# Olympus_v2.net
KiCad netlist of a schematic drawn in EAGLE
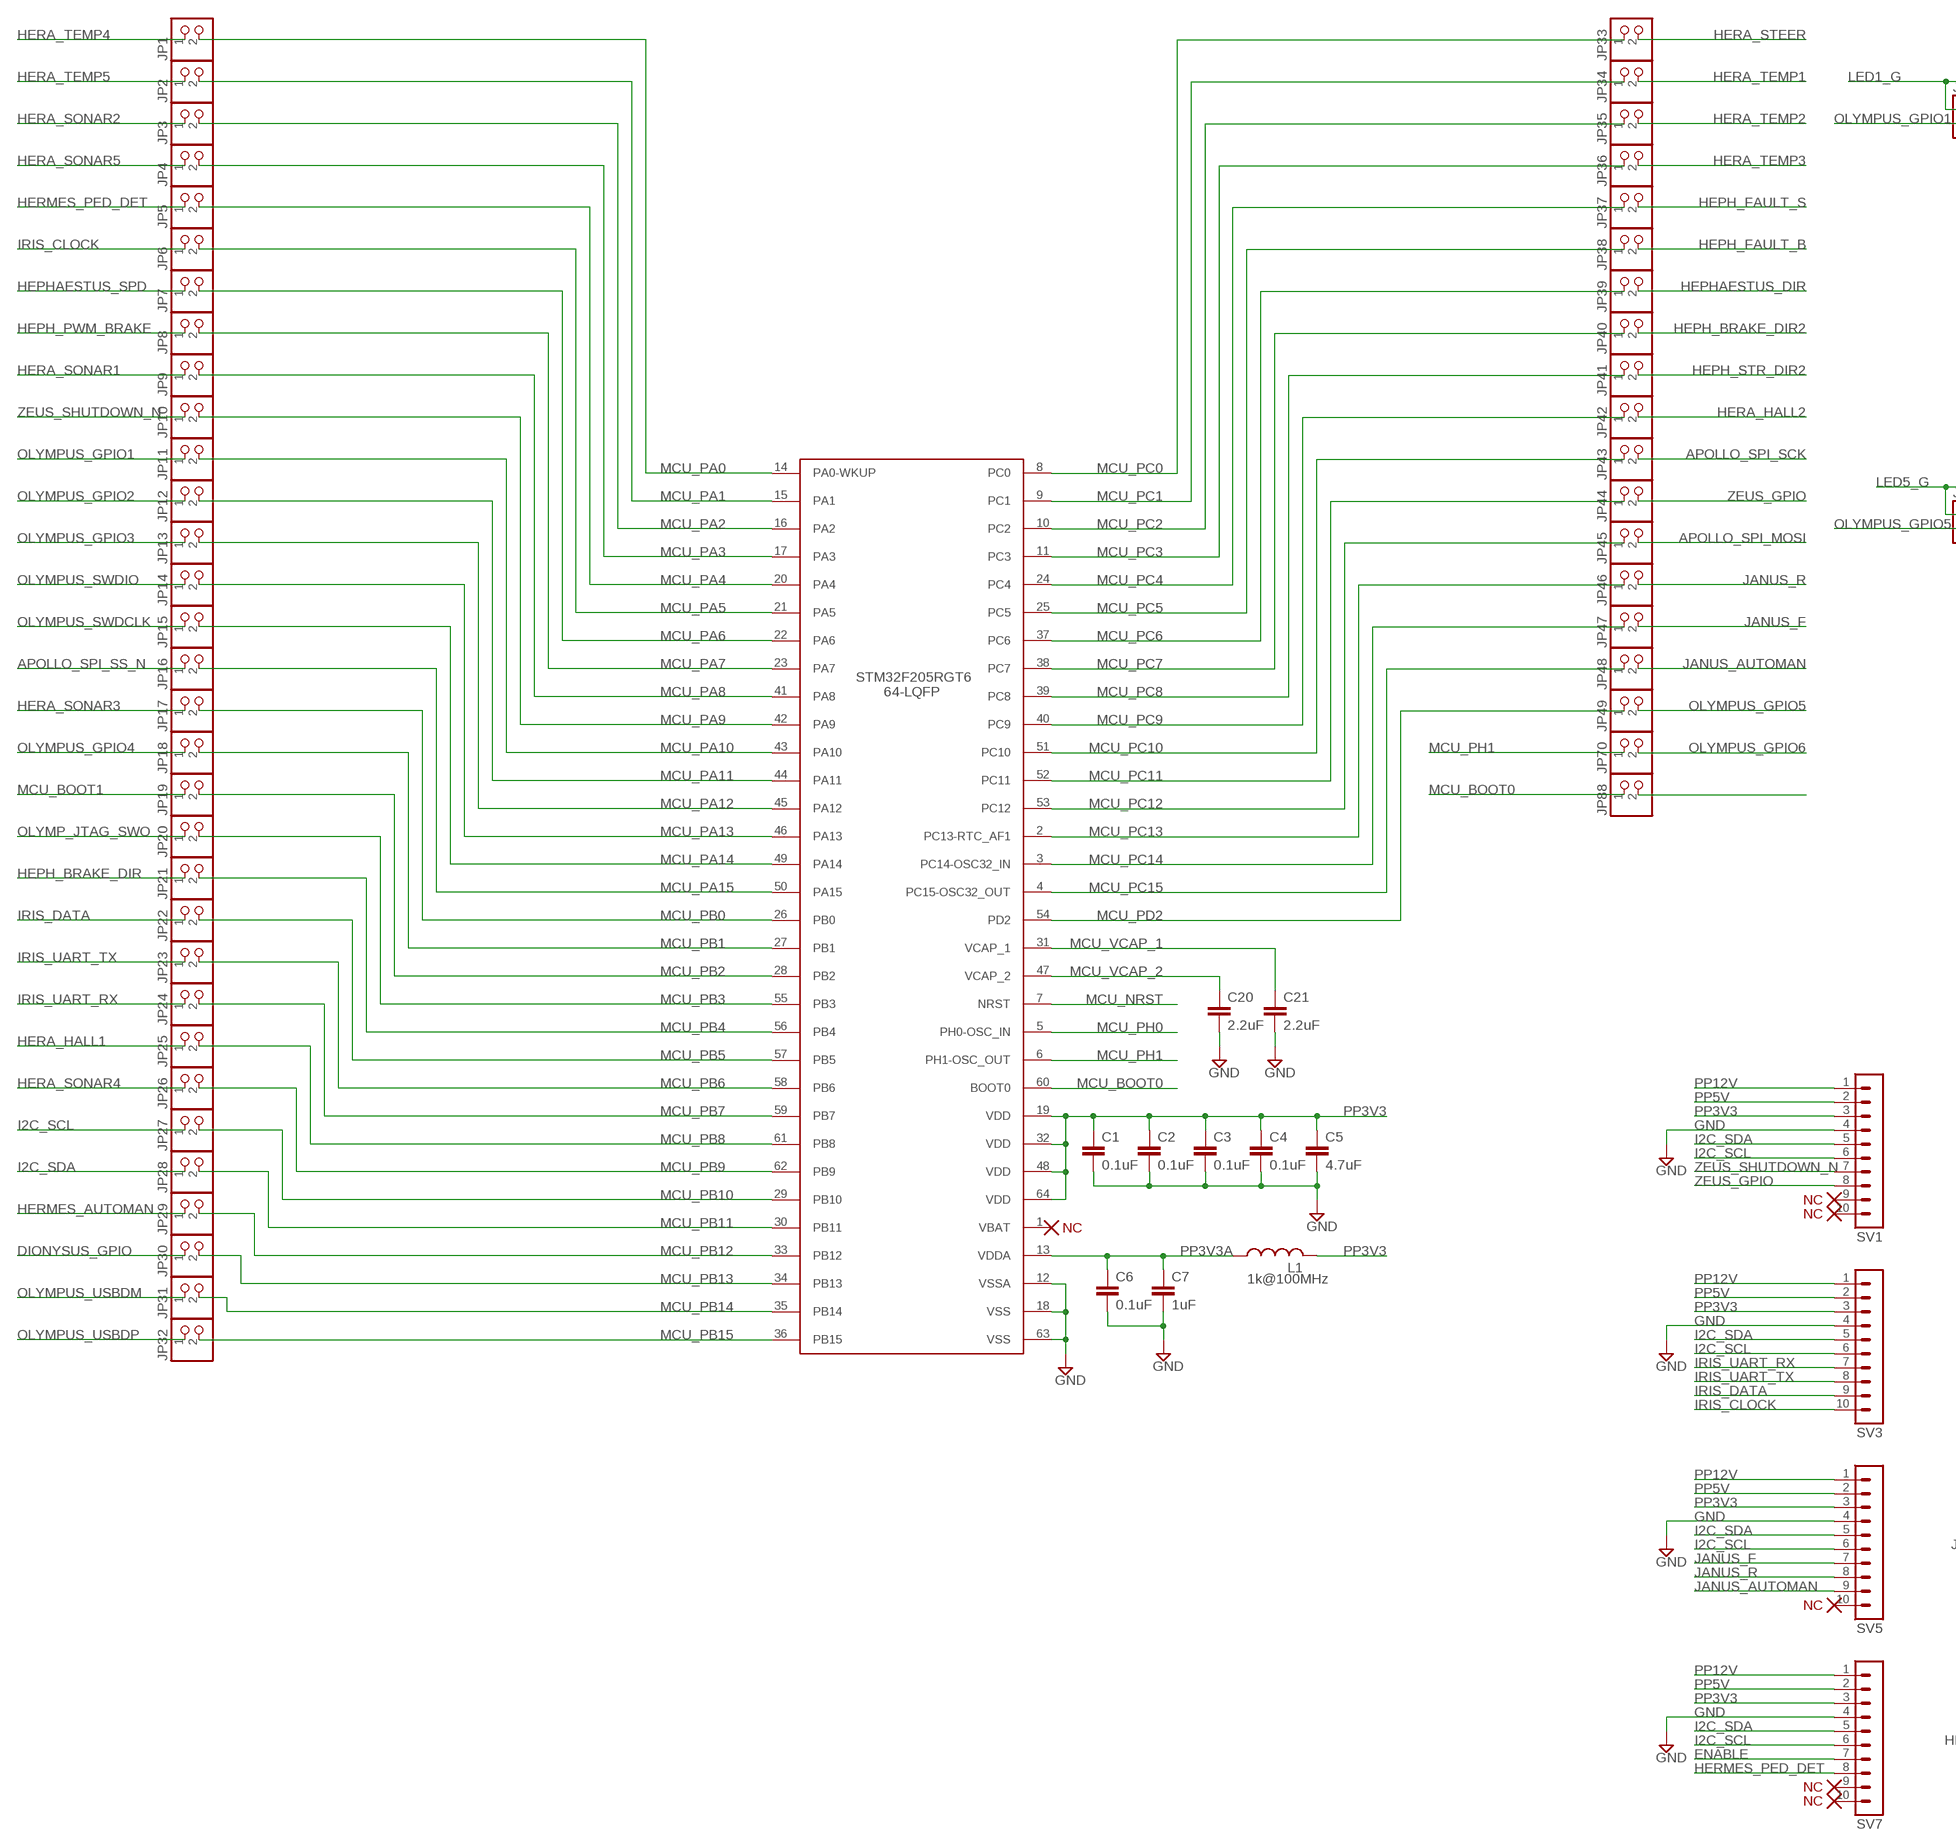
[diagram p0: schematic, sheet 1, part 1 of 2]
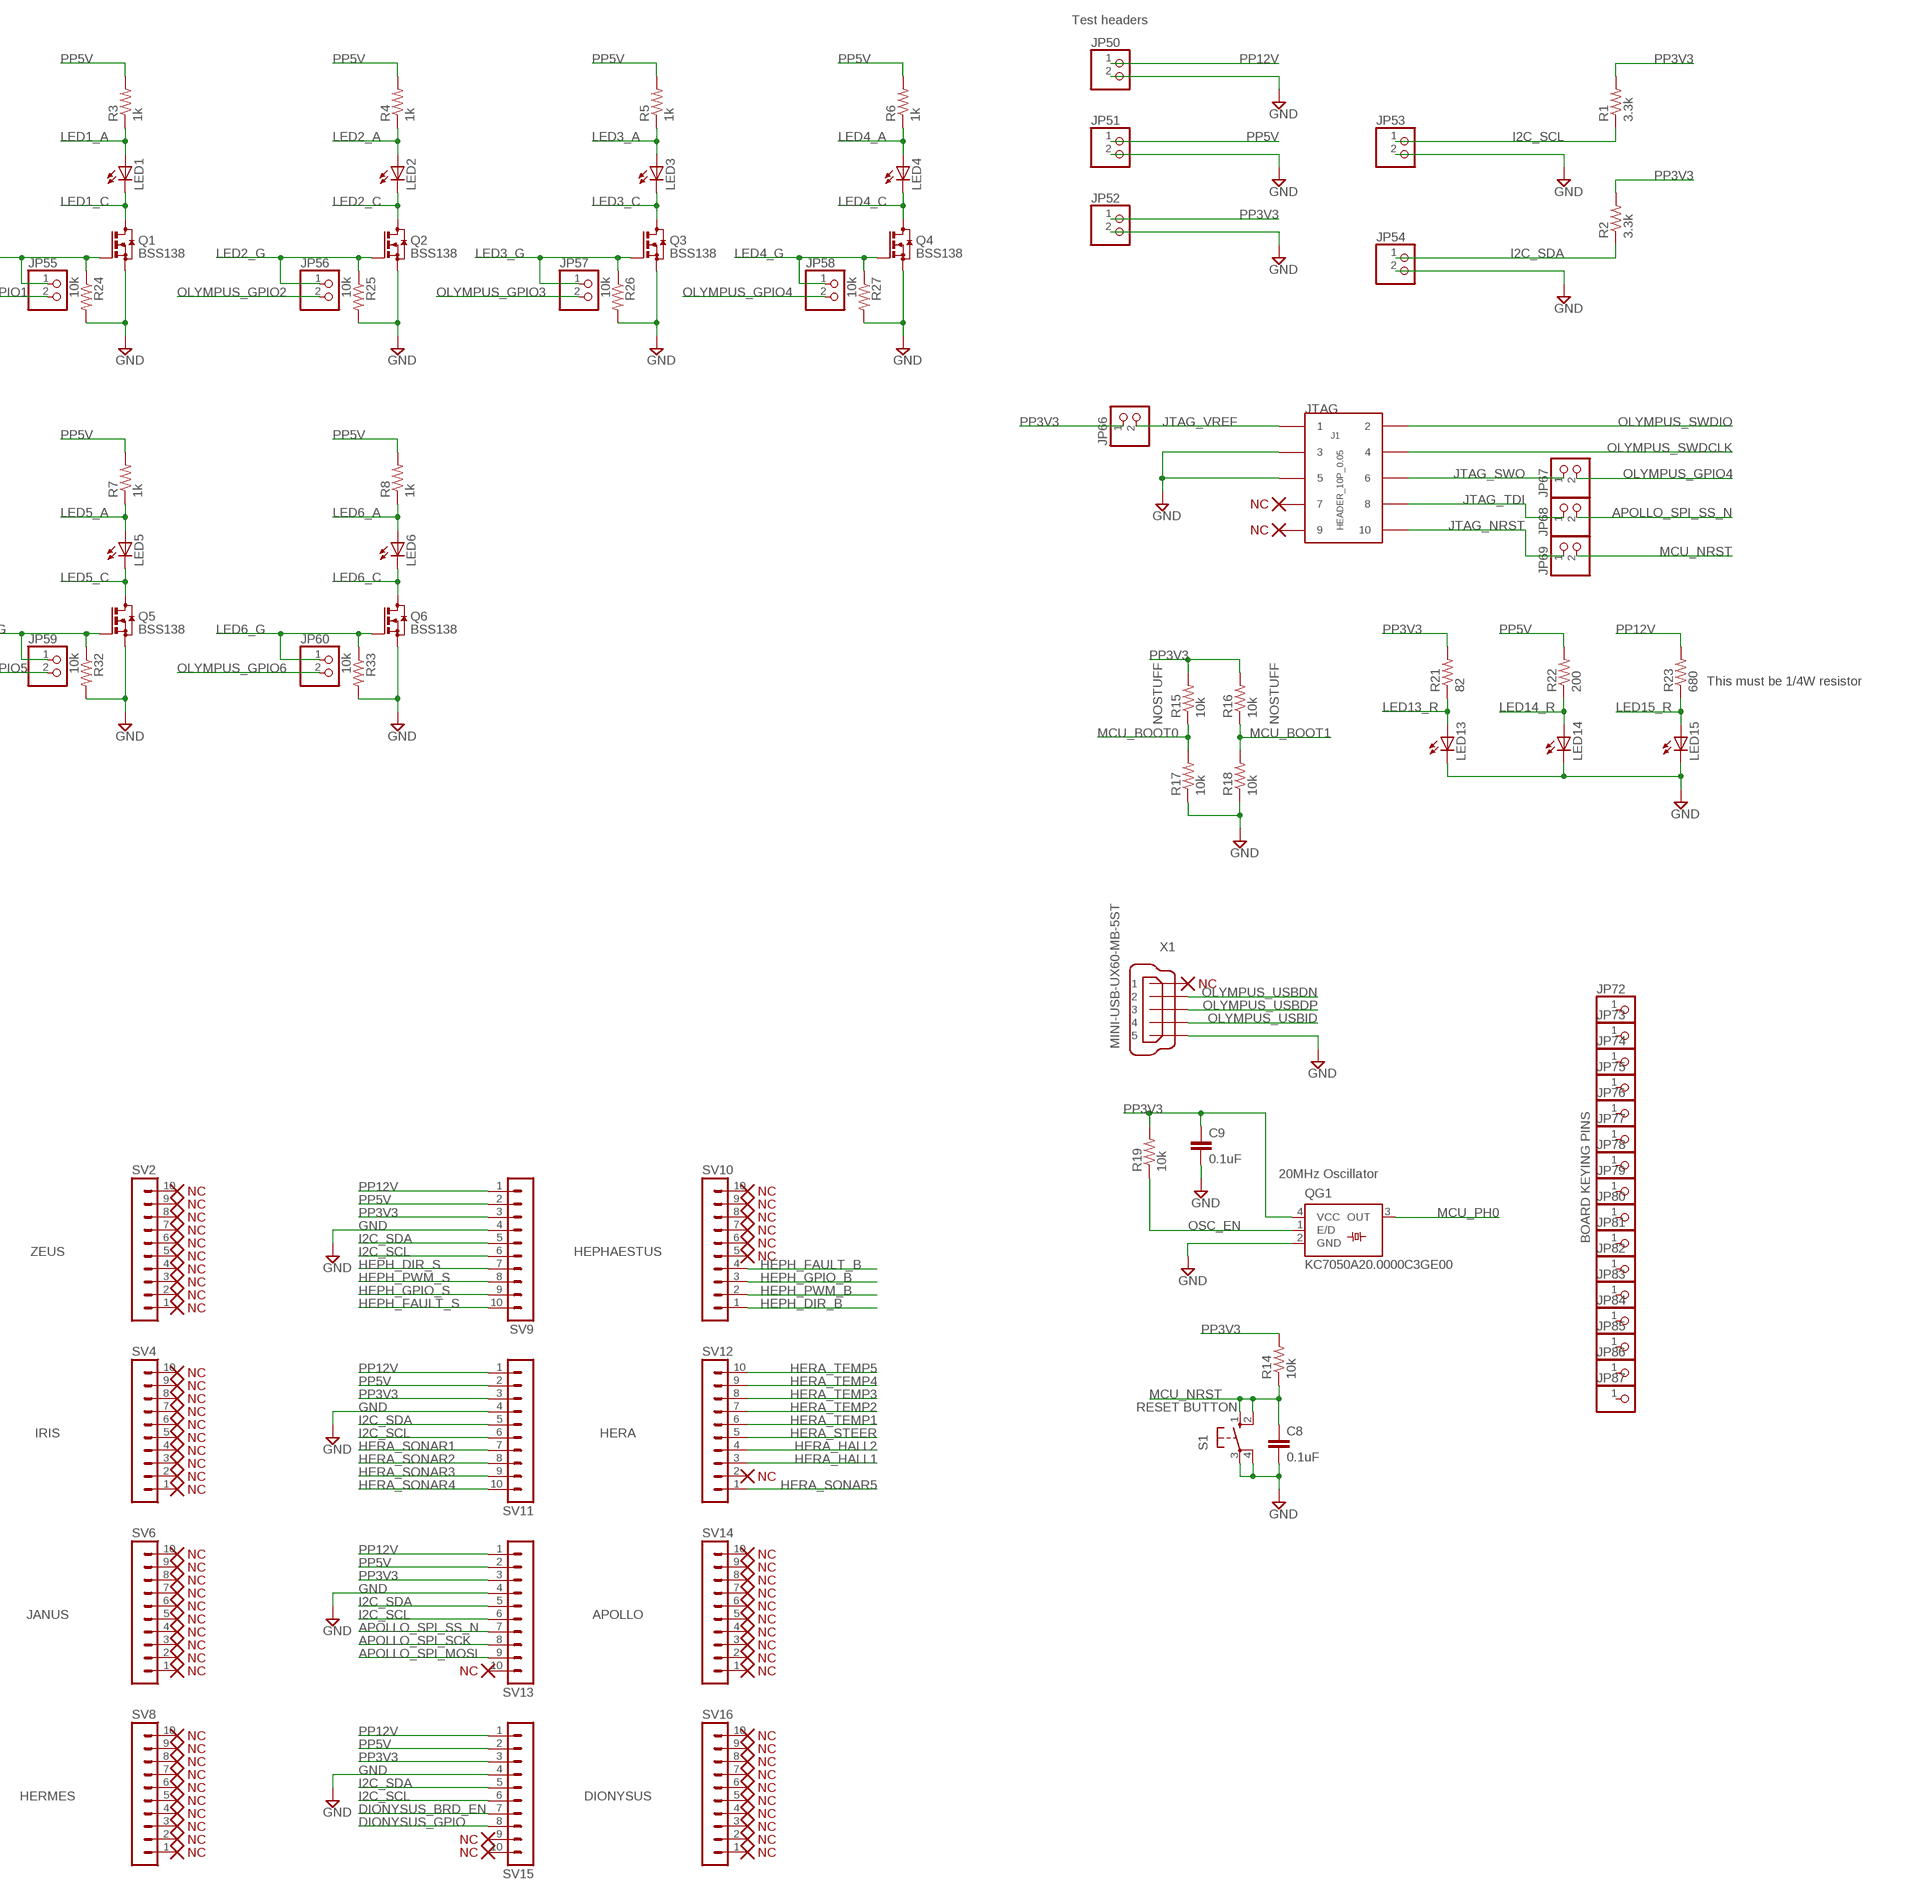
[diagram p1: schematic, sheet 1, part 2 of 2]

(export (version "E")
  (design (tool "Eeschema 10.0.6"))
  (components
    (comp (ref "C1")
      (value "0.1uF")
      (footprint "eagle-import:C0402")
      (libsource (lib "eagle-import") (part "C-EUC0402"))
    )
    (comp (ref "C2")
      (value "0.1uF")
      (footprint "eagle-import:C0402")
      (libsource (lib "eagle-import") (part "C-EUC0402"))
    )
    (comp (ref "C3")
      (value "0.1uF")
      (footprint "eagle-import:C0402")
      (libsource (lib "eagle-import") (part "C-EUC0402"))
    )
    (comp (ref "C4")
      (value "0.1uF")
      (footprint "eagle-import:C0402")
      (libsource (lib "eagle-import") (part "C-EUC0402"))
    )
    (comp (ref "C5")
      (value "4.7uF")
      (footprint "eagle-import:C0603")
      (libsource (lib "eagle-import") (part "C-EUC0603"))
    )
    (comp (ref "C6")
      (value "0.1uF")
      (footprint "eagle-import:C0402")
      (libsource (lib "eagle-import") (part "C-EUC0402"))
    )
    (comp (ref "C7")
      (value "1uF")
      (footprint "eagle-import:C0603")
      (libsource (lib "eagle-import") (part "C-EUC0603"))
    )
    (comp (ref "C8")
      (value "0.1uF")
      (footprint "eagle-import:C0402")
      (libsource (lib "eagle-import") (part "C-EUC0402"))
    )
    (comp (ref "C9")
      (value "0.1uF")
      (footprint "eagle-import:C0402")
      (libsource (lib "eagle-import") (part "C-EUC0402"))
    )
    (comp (ref "C20")
      (value "2.2uF")
      (footprint "eagle-import:C0402")
      (libsource (lib "eagle-import") (part "C-EUC0402"))
    )
    (comp (ref "C21")
      (value "2.2uF")
      (footprint "eagle-import:C0402")
      (libsource (lib "eagle-import") (part "C-EUC0402"))
    )
    (comp (ref "J1")
      (value "HEADER_10P_0.05")
      (footprint "eagle-import:HEADER_10P_0.05")
      (libsource (lib "eagle-import") (part "HEADER_10P_0.05"))
    )
    (comp (ref "JP1")
      (value "PINHD-1X2")
      (footprint "eagle-import:1X02")
      (libsource (lib "eagle-import") (part "PINHD-1X2"))
    )
    (comp (ref "JP2")
      (value "PINHD-1X2")
      (footprint "eagle-import:1X02")
      (libsource (lib "eagle-import") (part "PINHD-1X2"))
    )
    (comp (ref "JP3")
      (value "PINHD-1X2")
      (footprint "eagle-import:1X02")
      (libsource (lib "eagle-import") (part "PINHD-1X2"))
    )
    (comp (ref "JP4")
      (value "PINHD-1X2")
      (footprint "eagle-import:1X02")
      (libsource (lib "eagle-import") (part "PINHD-1X2"))
    )
    (comp (ref "JP5")
      (value "PINHD-1X2")
      (footprint "eagle-import:1X02")
      (libsource (lib "eagle-import") (part "PINHD-1X2"))
    )
    (comp (ref "JP6")
      (value "PINHD-1X2")
      (footprint "eagle-import:1X02")
      (libsource (lib "eagle-import") (part "PINHD-1X2"))
    )
    (comp (ref "JP7")
      (value "PINHD-1X2")
      (footprint "eagle-import:1X02")
      (libsource (lib "eagle-import") (part "PINHD-1X2"))
    )
    (comp (ref "JP8")
      (value "PINHD-1X2")
      (footprint "eagle-import:1X02")
      (libsource (lib "eagle-import") (part "PINHD-1X2"))
    )
    (comp (ref "JP9")
      (value "PINHD-1X2")
      (footprint "eagle-import:1X02")
      (libsource (lib "eagle-import") (part "PINHD-1X2"))
    )
    (comp (ref "JP10")
      (value "PINHD-1X2")
      (footprint "eagle-import:1X02")
      (libsource (lib "eagle-import") (part "PINHD-1X2"))
    )
    (comp (ref "JP11")
      (value "PINHD-1X2")
      (footprint "eagle-import:1X02")
      (libsource (lib "eagle-import") (part "PINHD-1X2"))
    )
    (comp (ref "JP12")
      (value "PINHD-1X2")
      (footprint "eagle-import:1X02")
      (libsource (lib "eagle-import") (part "PINHD-1X2"))
    )
    (comp (ref "JP13")
      (value "PINHD-1X2")
      (footprint "eagle-import:1X02")
      (libsource (lib "eagle-import") (part "PINHD-1X2"))
    )
    (comp (ref "JP14")
      (value "PINHD-1X2")
      (footprint "eagle-import:1X02")
      (libsource (lib "eagle-import") (part "PINHD-1X2"))
    )
    (comp (ref "JP15")
      (value "PINHD-1X2")
      (footprint "eagle-import:1X02")
      (libsource (lib "eagle-import") (part "PINHD-1X2"))
    )
    (comp (ref "JP16")
      (value "PINHD-1X2")
      (footprint "eagle-import:1X02")
      (libsource (lib "eagle-import") (part "PINHD-1X2"))
    )
    (comp (ref "JP17")
      (value "PINHD-1X2")
      (footprint "eagle-import:1X02")
      (libsource (lib "eagle-import") (part "PINHD-1X2"))
    )
    (comp (ref "JP18")
      (value "PINHD-1X2")
      (footprint "eagle-import:1X02")
      (libsource (lib "eagle-import") (part "PINHD-1X2"))
    )
    (comp (ref "JP19")
      (value "PINHD-1X2")
      (footprint "eagle-import:1X02")
      (libsource (lib "eagle-import") (part "PINHD-1X2"))
    )
    (comp (ref "JP20")
      (value "PINHD-1X2")
      (footprint "eagle-import:1X02")
      (libsource (lib "eagle-import") (part "PINHD-1X2"))
    )
    (comp (ref "JP21")
      (value "PINHD-1X2")
      (footprint "eagle-import:1X02")
      (libsource (lib "eagle-import") (part "PINHD-1X2"))
    )
    (comp (ref "JP22")
      (value "PINHD-1X2")
      (footprint "eagle-import:1X02")
      (libsource (lib "eagle-import") (part "PINHD-1X2"))
    )
    (comp (ref "JP23")
      (value "PINHD-1X2")
      (footprint "eagle-import:1X02")
      (libsource (lib "eagle-import") (part "PINHD-1X2"))
    )
    (comp (ref "JP24")
      (value "PINHD-1X2")
      (footprint "eagle-import:1X02")
      (libsource (lib "eagle-import") (part "PINHD-1X2"))
    )
    (comp (ref "JP25")
      (value "PINHD-1X2")
      (footprint "eagle-import:1X02")
      (libsource (lib "eagle-import") (part "PINHD-1X2"))
    )
    (comp (ref "JP26")
      (value "PINHD-1X2")
      (footprint "eagle-import:1X02")
      (libsource (lib "eagle-import") (part "PINHD-1X2"))
    )
    (comp (ref "JP27")
      (value "PINHD-1X2")
      (footprint "eagle-import:1X02")
      (libsource (lib "eagle-import") (part "PINHD-1X2"))
    )
    (comp (ref "JP28")
      (value "PINHD-1X2")
      (footprint "eagle-import:1X02")
      (libsource (lib "eagle-import") (part "PINHD-1X2"))
    )
    (comp (ref "JP29")
      (value "PINHD-1X2")
      (footprint "eagle-import:1X02")
      (libsource (lib "eagle-import") (part "PINHD-1X2"))
    )
    (comp (ref "JP30")
      (value "PINHD-1X2")
      (footprint "eagle-import:1X02")
      (libsource (lib "eagle-import") (part "PINHD-1X2"))
    )
    (comp (ref "JP31")
      (value "PINHD-1X2")
      (footprint "eagle-import:1X02")
      (libsource (lib "eagle-import") (part "PINHD-1X2"))
    )
    (comp (ref "JP32")
      (value "PINHD-1X2")
      (footprint "eagle-import:1X02")
      (libsource (lib "eagle-import") (part "PINHD-1X2"))
    )
    (comp (ref "JP33")
      (value "PINHD-1X2")
      (footprint "eagle-import:1X02")
      (libsource (lib "eagle-import") (part "PINHD-1X2"))
    )
    (comp (ref "JP34")
      (value "PINHD-1X2")
      (footprint "eagle-import:1X02")
      (libsource (lib "eagle-import") (part "PINHD-1X2"))
    )
    (comp (ref "JP35")
      (value "PINHD-1X2")
      (footprint "eagle-import:1X02")
      (libsource (lib "eagle-import") (part "PINHD-1X2"))
    )
    (comp (ref "JP36")
      (value "PINHD-1X2")
      (footprint "eagle-import:1X02")
      (libsource (lib "eagle-import") (part "PINHD-1X2"))
    )
    (comp (ref "JP37")
      (value "PINHD-1X2")
      (footprint "eagle-import:1X02")
      (libsource (lib "eagle-import") (part "PINHD-1X2"))
    )
    (comp (ref "JP38")
      (value "PINHD-1X2")
      (footprint "eagle-import:1X02")
      (libsource (lib "eagle-import") (part "PINHD-1X2"))
    )
    (comp (ref "JP39")
      (value "PINHD-1X2")
      (footprint "eagle-import:1X02")
      (libsource (lib "eagle-import") (part "PINHD-1X2"))
    )
    (comp (ref "JP40")
      (value "PINHD-1X2")
      (footprint "eagle-import:1X02")
      (libsource (lib "eagle-import") (part "PINHD-1X2"))
    )
    (comp (ref "JP41")
      (value "PINHD-1X2")
      (footprint "eagle-import:1X02")
      (libsource (lib "eagle-import") (part "PINHD-1X2"))
    )
    (comp (ref "JP42")
      (value "PINHD-1X2")
      (footprint "eagle-import:1X02")
      (libsource (lib "eagle-import") (part "PINHD-1X2"))
    )
    (comp (ref "JP43")
      (value "PINHD-1X2")
      (footprint "eagle-import:1X02")
      (libsource (lib "eagle-import") (part "PINHD-1X2"))
    )
    (comp (ref "JP44")
      (value "PINHD-1X2")
      (footprint "eagle-import:1X02")
      (libsource (lib "eagle-import") (part "PINHD-1X2"))
    )
    (comp (ref "JP45")
      (value "PINHD-1X2")
      (footprint "eagle-import:1X02")
      (libsource (lib "eagle-import") (part "PINHD-1X2"))
    )
    (comp (ref "JP46")
      (value "PINHD-1X2")
      (footprint "eagle-import:1X02")
      (libsource (lib "eagle-import") (part "PINHD-1X2"))
    )
    (comp (ref "JP47")
      (value "PINHD-1X2")
      (footprint "eagle-import:1X02")
      (libsource (lib "eagle-import") (part "PINHD-1X2"))
    )
    (comp (ref "JP48")
      (value "PINHD-1X2")
      (footprint "eagle-import:1X02")
      (libsource (lib "eagle-import") (part "PINHD-1X2"))
    )
    (comp (ref "JP49")
      (value "PINHD-1X2")
      (footprint "eagle-import:1X02")
      (libsource (lib "eagle-import") (part "PINHD-1X2"))
    )
    (comp (ref "JP50")
      (value "PINHD-1X2")
      (footprint "eagle-import:1X02")
      (libsource (lib "eagle-import") (part "PINHD-1X2"))
    )
    (comp (ref "JP51")
      (value "PINHD-1X2")
      (footprint "eagle-import:1X02")
      (libsource (lib "eagle-import") (part "PINHD-1X2"))
    )
    (comp (ref "JP52")
      (value "PINHD-1X2")
      (footprint "eagle-import:1X02")
      (libsource (lib "eagle-import") (part "PINHD-1X2"))
    )
    (comp (ref "JP53")
      (value "PINHD-1X2")
      (footprint "eagle-import:1X02")
      (libsource (lib "eagle-import") (part "PINHD-1X2"))
    )
    (comp (ref "JP54")
      (value "PINHD-1X2")
      (footprint "eagle-import:1X02")
      (libsource (lib "eagle-import") (part "PINHD-1X2"))
    )
    (comp (ref "JP55")
      (value "PINHD-1X2")
      (footprint "eagle-import:1X02")
      (libsource (lib "eagle-import") (part "PINHD-1X2"))
    )
    (comp (ref "JP56")
      (value "PINHD-1X2")
      (footprint "eagle-import:1X02")
      (libsource (lib "eagle-import") (part "PINHD-1X2"))
    )
    (comp (ref "JP57")
      (value "PINHD-1X2")
      (footprint "eagle-import:1X02")
      (libsource (lib "eagle-import") (part "PINHD-1X2"))
    )
    (comp (ref "JP58")
      (value "PINHD-1X2")
      (footprint "eagle-import:1X02")
      (libsource (lib "eagle-import") (part "PINHD-1X2"))
    )
    (comp (ref "JP59")
      (value "PINHD-1X2")
      (footprint "eagle-import:1X02")
      (libsource (lib "eagle-import") (part "PINHD-1X2"))
    )
    (comp (ref "JP60")
      (value "PINHD-1X2")
      (footprint "eagle-import:1X02")
      (libsource (lib "eagle-import") (part "PINHD-1X2"))
    )
    (comp (ref "JP66")
      (value "PINHD-1X2")
      (footprint "eagle-import:1X02")
      (libsource (lib "eagle-import") (part "PINHD-1X2"))
    )
    (comp (ref "JP67")
      (value "PINHD-1X2")
      (footprint "eagle-import:1X02")
      (libsource (lib "eagle-import") (part "PINHD-1X2"))
    )
    (comp (ref "JP68")
      (value "PINHD-1X2")
      (footprint "eagle-import:1X02")
      (libsource (lib "eagle-import") (part "PINHD-1X2"))
    )
    (comp (ref "JP69")
      (value "PINHD-1X2")
      (footprint "eagle-import:1X02")
      (libsource (lib "eagle-import") (part "PINHD-1X2"))
    )
    (comp (ref "JP70")
      (value "PINHD-1X2")
      (footprint "eagle-import:1X02")
      (libsource (lib "eagle-import") (part "PINHD-1X2"))
    )
    (comp (ref "JP72")
      (value "PINHD-1X1")
      (footprint "eagle-import:1X01")
      (libsource (lib "eagle-import") (part "PINHD-1X1"))
    )
    (comp (ref "JP73")
      (value "PINHD-1X1")
      (footprint "eagle-import:1X01")
      (libsource (lib "eagle-import") (part "PINHD-1X1"))
    )
    (comp (ref "JP74")
      (value "PINHD-1X1")
      (footprint "eagle-import:1X01")
      (libsource (lib "eagle-import") (part "PINHD-1X1"))
    )
    (comp (ref "JP75")
      (value "PINHD-1X1")
      (footprint "eagle-import:1X01")
      (libsource (lib "eagle-import") (part "PINHD-1X1"))
    )
    (comp (ref "JP76")
      (value "PINHD-1X1")
      (footprint "eagle-import:1X01")
      (libsource (lib "eagle-import") (part "PINHD-1X1"))
    )
    (comp (ref "JP77")
      (value "PINHD-1X1")
      (footprint "eagle-import:1X01")
      (libsource (lib "eagle-import") (part "PINHD-1X1"))
    )
    (comp (ref "JP78")
      (value "PINHD-1X1")
      (footprint "eagle-import:1X01")
      (libsource (lib "eagle-import") (part "PINHD-1X1"))
    )
    (comp (ref "JP79")
      (value "PINHD-1X1")
      (footprint "eagle-import:1X01")
      (libsource (lib "eagle-import") (part "PINHD-1X1"))
    )
    (comp (ref "JP80")
      (value "PINHD-1X1")
      (footprint "eagle-import:1X01")
      (libsource (lib "eagle-import") (part "PINHD-1X1"))
    )
    (comp (ref "JP81")
      (value "PINHD-1X1")
      (footprint "eagle-import:1X01")
      (libsource (lib "eagle-import") (part "PINHD-1X1"))
    )
    (comp (ref "JP82")
      (value "PINHD-1X1")
      (footprint "eagle-import:1X01")
      (libsource (lib "eagle-import") (part "PINHD-1X1"))
    )
    (comp (ref "JP83")
      (value "PINHD-1X1")
      (footprint "eagle-import:1X01")
      (libsource (lib "eagle-import") (part "PINHD-1X1"))
    )
    (comp (ref "JP84")
      (value "PINHD-1X1")
      (footprint "eagle-import:1X01")
      (libsource (lib "eagle-import") (part "PINHD-1X1"))
    )
    (comp (ref "JP85")
      (value "PINHD-1X1")
      (footprint "eagle-import:1X01")
      (libsource (lib "eagle-import") (part "PINHD-1X1"))
    )
    (comp (ref "JP86")
      (value "PINHD-1X1")
      (footprint "eagle-import:1X01")
      (libsource (lib "eagle-import") (part "PINHD-1X1"))
    )
    (comp (ref "JP87")
      (value "PINHD-1X1")
      (footprint "eagle-import:1X01")
      (libsource (lib "eagle-import") (part "PINHD-1X1"))
    )
    (comp (ref "JP88")
      (value "PINHD-1X2")
      (footprint "eagle-import:1X02")
      (libsource (lib "eagle-import") (part "PINHD-1X2"))
    )
    (comp (ref "L1")
      (value "L-USL0201")
      (footprint "eagle-import:L0201")
      (libsource (lib "eagle-import") (part "L-USL0201"))
    )
    (comp (ref "LED1")
      (value "LEDCHIP-LED0603")
      (footprint "eagle-import:CHIP-LED0603")
      (libsource (lib "eagle-import") (part "LEDCHIP-LED0603"))
    )
    (comp (ref "LED2")
      (value "LEDCHIP-LED0603")
      (footprint "eagle-import:CHIP-LED0603")
      (libsource (lib "eagle-import") (part "LEDCHIP-LED0603"))
    )
    (comp (ref "LED3")
      (value "LEDCHIP-LED0603")
      (footprint "eagle-import:CHIP-LED0603")
      (libsource (lib "eagle-import") (part "LEDCHIP-LED0603"))
    )
    (comp (ref "LED4")
      (value "LEDCHIP-LED0603")
      (footprint "eagle-import:CHIP-LED0603")
      (libsource (lib "eagle-import") (part "LEDCHIP-LED0603"))
    )
    (comp (ref "LED5")
      (value "LEDCHIP-LED0603")
      (footprint "eagle-import:CHIP-LED0603")
      (libsource (lib "eagle-import") (part "LEDCHIP-LED0603"))
    )
    (comp (ref "LED6")
      (value "LEDCHIP-LED0603")
      (footprint "eagle-import:CHIP-LED0603")
      (libsource (lib "eagle-import") (part "LEDCHIP-LED0603"))
    )
    (comp (ref "LED13")
      (value "LEDCHIP-LED0603")
      (footprint "eagle-import:CHIP-LED0603")
      (libsource (lib "eagle-import") (part "LEDCHIP-LED0603"))
    )
    (comp (ref "LED14")
      (value "LEDCHIP-LED0603")
      (footprint "eagle-import:CHIP-LED0603")
      (libsource (lib "eagle-import") (part "LEDCHIP-LED0603"))
    )
    (comp (ref "LED15")
      (value "LEDCHIP-LED0603")
      (footprint "eagle-import:CHIP-LED0603")
      (libsource (lib "eagle-import") (part "LEDCHIP-LED0603"))
    )
    (comp (ref "Q1")
      (value "BSS138")
      (footprint "eagle-import:SOT23")
      (libsource (lib "eagle-import") (part "BSS123"))
    )
    (comp (ref "Q2")
      (value "BSS138")
      (footprint "eagle-import:SOT23")
      (libsource (lib "eagle-import") (part "BSS123"))
    )
    (comp (ref "Q3")
      (value "BSS138")
      (footprint "eagle-import:SOT23")
      (libsource (lib "eagle-import") (part "BSS123"))
    )
    (comp (ref "Q4")
      (value "BSS138")
      (footprint "eagle-import:SOT23")
      (libsource (lib "eagle-import") (part "BSS123"))
    )
    (comp (ref "Q5")
      (value "BSS138")
      (footprint "eagle-import:SOT23")
      (libsource (lib "eagle-import") (part "BSS123"))
    )
    (comp (ref "Q6")
      (value "BSS138")
      (footprint "eagle-import:SOT23")
      (libsource (lib "eagle-import") (part "BSS123"))
    )
    (comp (ref "QG1")
      (value "KC7050A20.0000C3GE00")
      (footprint "eagle-import:SM77H")
      (libsource (lib "eagle-import") (part "SM77H"))
    )
    (comp (ref "R1")
      (value "3.3k")
      (footprint "eagle-import:R0603")
      (libsource (lib "eagle-import") (part "R-US_R0603"))
    )
    (comp (ref "R2")
      (value "3.3k")
      (footprint "eagle-import:R0603")
      (libsource (lib "eagle-import") (part "R-US_R0603"))
    )
    (comp (ref "R3")
      (value "1k")
      (footprint "eagle-import:R0603")
      (libsource (lib "eagle-import") (part "resistor_R-US_R0603"))
    )
    (comp (ref "R4")
      (value "1k")
      (footprint "eagle-import:R0603")
      (libsource (lib "eagle-import") (part "resistor_R-US_R0603"))
    )
    (comp (ref "R5")
      (value "1k")
      (footprint "eagle-import:R0603")
      (libsource (lib "eagle-import") (part "resistor_R-US_R0603"))
    )
    (comp (ref "R6")
      (value "1k")
      (footprint "eagle-import:R0603")
      (libsource (lib "eagle-import") (part "resistor_R-US_R0603"))
    )
    (comp (ref "R7")
      (value "1k")
      (footprint "eagle-import:R0603")
      (libsource (lib "eagle-import") (part "resistor_R-US_R0603"))
    )
    (comp (ref "R8")
      (value "1k")
      (footprint "eagle-import:R0603")
      (libsource (lib "eagle-import") (part "resistor_R-US_R0603"))
    )
    (comp (ref "R14")
      (value "10k")
      (footprint "eagle-import:R0603")
      (libsource (lib "eagle-import") (part "R-US_R0603"))
    )
    (comp (ref "R15")
      (value "10k")
      (footprint "eagle-import:R0603")
      (fields (field (name "BOMOPTION") "NOSTUFF"))
      (libsource (lib "eagle-import") (part "R-US_R0603"))
    )
    (comp (ref "R16")
      (value "10k")
      (footprint "eagle-import:R0603")
      (fields (field (name "BOMOPTION") "NOSTUFF"))
      (libsource (lib "eagle-import") (part "R-US_R0603"))
    )
    (comp (ref "R17")
      (value "10k")
      (footprint "eagle-import:R0603")
      (libsource (lib "eagle-import") (part "R-US_R0603"))
    )
    (comp (ref "R18")
      (value "10k")
      (footprint "eagle-import:R0603")
      (libsource (lib "eagle-import") (part "R-US_R0603"))
    )
    (comp (ref "R19")
      (value "10k")
      (footprint "eagle-import:R0603")
      (libsource (lib "eagle-import") (part "R-US_R0603"))
    )
    (comp (ref "R21")
      (value "82")
      (footprint "eagle-import:R0603")
      (libsource (lib "eagle-import") (part "resistor_R-US_R0603"))
    )
    (comp (ref "R22")
      (value "200")
      (footprint "eagle-import:R0603")
      (libsource (lib "eagle-import") (part "resistor_R-US_R0603"))
    )
    (comp (ref "R23")
      (value "680")
      (footprint "eagle-import:R0603")
      (libsource (lib "eagle-import") (part "resistor_R-US_R0603"))
    )
    (comp (ref "R24")
      (value "10k")
      (footprint "eagle-import:R0603")
      (libsource (lib "eagle-import") (part "resistor_R-US_R0603"))
    )
    (comp (ref "R25")
      (value "10k")
      (footprint "eagle-import:R0603")
      (libsource (lib "eagle-import") (part "resistor_R-US_R0603"))
    )
    (comp (ref "R26")
      (value "10k")
      (footprint "eagle-import:R0603")
      (libsource (lib "eagle-import") (part "resistor_R-US_R0603"))
    )
    (comp (ref "R27")
      (value "10k")
      (footprint "eagle-import:R0603")
      (libsource (lib "eagle-import") (part "resistor_R-US_R0603"))
    )
    (comp (ref "R32")
      (value "10k")
      (footprint "eagle-import:R0603")
      (libsource (lib "eagle-import") (part "resistor_R-US_R0603"))
    )
    (comp (ref "R33")
      (value "10k")
      (footprint "eagle-import:R0603")
      (libsource (lib "eagle-import") (part "resistor_R-US_R0603"))
    )
    (comp (ref "S1")
      (value "10-XX")
      (footprint "eagle-import:B3F-10XX")
      (fields (field (name "MPN") "B3F-1000"))
      (libsource (lib "eagle-import") (part "10-XX"))
    )
    (comp (ref "SV1")
      (value "MA10-1")
      (footprint "eagle-import:MA10-1")
      (libsource (lib "eagle-import") (part "MA10-1"))
    )
    (comp (ref "SV2")
      (value "MA10-1")
      (footprint "eagle-import:MA10-1")
      (libsource (lib "eagle-import") (part "MA10-1"))
    )
    (comp (ref "SV3")
      (value "MA10-1")
      (footprint "eagle-import:MA10-1")
      (libsource (lib "eagle-import") (part "MA10-1"))
    )
    (comp (ref "SV4")
      (value "MA10-1")
      (footprint "eagle-import:MA10-1")
      (libsource (lib "eagle-import") (part "MA10-1"))
    )
    (comp (ref "SV5")
      (value "MA10-1")
      (footprint "eagle-import:MA10-1")
      (libsource (lib "eagle-import") (part "MA10-1"))
    )
    (comp (ref "SV6")
      (value "MA10-1")
      (footprint "eagle-import:MA10-1")
      (libsource (lib "eagle-import") (part "MA10-1"))
    )
    (comp (ref "SV7")
      (value "MA10-1")
      (footprint "eagle-import:MA10-1")
      (libsource (lib "eagle-import") (part "MA10-1"))
    )
    (comp (ref "SV8")
      (value "MA10-1")
      (footprint "eagle-import:MA10-1")
      (libsource (lib "eagle-import") (part "MA10-1"))
    )
    (comp (ref "SV9")
      (value "MA10-1")
      (footprint "eagle-import:MA10-1")
      (libsource (lib "eagle-import") (part "MA10-1"))
    )
    (comp (ref "SV10")
      (value "MA10-1")
      (footprint "eagle-import:MA10-1")
      (libsource (lib "eagle-import") (part "MA10-1"))
    )
    (comp (ref "SV11")
      (value "MA10-1")
      (footprint "eagle-import:MA10-1")
      (libsource (lib "eagle-import") (part "MA10-1"))
    )
    (comp (ref "SV12")
      (value "MA10-1")
      (footprint "eagle-import:MA10-1")
      (libsource (lib "eagle-import") (part "MA10-1"))
    )
    (comp (ref "SV13")
      (value "MA10-1")
      (footprint "eagle-import:MA10-1")
      (libsource (lib "eagle-import") (part "MA10-1"))
    )
    (comp (ref "SV14")
      (value "MA10-1")
      (footprint "eagle-import:MA10-1")
      (libsource (lib "eagle-import") (part "MA10-1"))
    )
    (comp (ref "SV15")
      (value "MA10-1")
      (footprint "eagle-import:MA10-1")
      (libsource (lib "eagle-import") (part "MA10-1"))
    )
    (comp (ref "SV16")
      (value "MA10-1")
      (footprint "eagle-import:MA10-1")
      (libsource (lib "eagle-import") (part "MA10-1"))
    )
    (comp (ref "U1")
      (value "STM32F205RGT6")
      (footprint "eagle-import:LQFP-ST-64-2")
      (libsource (lib "eagle-import") (part "STM32F205RGT6"))
    )
    (comp (ref "X1")
      (value "MINI-USB-UX60-MB-5ST")
      (footprint "eagle-import:UX60-MB-5ST")
      (libsource (lib "eagle-import") (part "MINI-USB-UX60-MB-5ST"))
    )
  )
  (nets
    (net (code "1") (name "/APOLLO_SPI_MOSI") (class "Default")
      (node (ref "JP45") (pin "2") (pinfunction "2_2") (pintype "passive"))
      (node (ref "SV13") (pin "9") (pinfunction "9_9") (pintype "passive"))
    )
    (net (code "2") (name "/APOLLO_SPI_SCK") (class "Default")
      (node (ref "JP43") (pin "2") (pinfunction "2_2") (pintype "passive"))
      (node (ref "SV13") (pin "8") (pinfunction "8_8") (pintype "passive"))
    )
    (net (code "3") (name "/APOLLO_SPI_SS_N") (class "Default")
      (node (ref "JP16") (pin "1") (pinfunction "1_1") (pintype "passive"))
      (node (ref "JP68") (pin "2") (pinfunction "2_2") (pintype "passive"))
      (node (ref "SV13") (pin "7") (pinfunction "7_7") (pintype "passive"))
    )
    (net (code "4") (name "/DIONYSUS_BRD_EN") (class "Default")
      (node (ref "SV15") (pin "7") (pinfunction "7_7") (pintype "passive"))
    )
    (net (code "5") (name "/DIONYSUS_GPIO") (class "Default")
      (node (ref "JP30") (pin "1") (pinfunction "1_1") (pintype "passive"))
      (node (ref "SV15") (pin "8") (pinfunction "8_8") (pintype "passive"))
    )
    (net (code "6") (name "/ENABLE") (class "Default")
      (node (ref "SV7") (pin "7") (pinfunction "7_7") (pintype "passive"))
    )
    (net (code "7") (name "/HEPHAESTUS_DIR") (class "Default")
      (node (ref "JP39") (pin "2") (pinfunction "2_2") (pintype "passive"))
    )
    (net (code "8") (name "/HEPHAESTUS_SPD") (class "Default")
      (node (ref "JP7") (pin "1") (pinfunction "1_1") (pintype "passive"))
    )
    (net (code "9") (name "/HEPH_BRAKE_DIR") (class "Default")
      (node (ref "JP21") (pin "1") (pinfunction "1_1") (pintype "passive"))
    )
    (net (code "10") (name "/HEPH_BRAKE_DIR2") (class "Default")
      (node (ref "JP40") (pin "2") (pinfunction "2_2") (pintype "passive"))
    )
    (net (code "11") (name "/HEPH_DIR_B") (class "Default")
      (node (ref "SV10") (pin "1") (pinfunction "1_1") (pintype "passive"))
    )
    (net (code "12") (name "/HEPH_DIR_S") (class "Default")
      (node (ref "SV9") (pin "7") (pinfunction "7_7") (pintype "passive"))
    )
    (net (code "13") (name "/HEPH_FAULT_B") (class "Default")
      (node (ref "JP38") (pin "2") (pinfunction "2_2") (pintype "passive"))
      (node (ref "SV10") (pin "4") (pinfunction "4_4") (pintype "passive"))
    )
    (net (code "14") (name "/HEPH_FAULT_S") (class "Default")
      (node (ref "JP37") (pin "2") (pinfunction "2_2") (pintype "passive"))
      (node (ref "SV9") (pin "10") (pinfunction "10_10") (pintype "passive"))
    )
    (net (code "15") (name "/HEPH_GPIO_B") (class "Default")
      (node (ref "SV10") (pin "3") (pinfunction "3_3") (pintype "passive"))
    )
    (net (code "16") (name "/HEPH_GPIO_S") (class "Default")
      (node (ref "SV9") (pin "9") (pinfunction "9_9") (pintype "passive"))
    )
    (net (code "17") (name "/HEPH_PWM_B") (class "Default")
      (node (ref "SV10") (pin "2") (pinfunction "2_2") (pintype "passive"))
    )
    (net (code "18") (name "/HEPH_PWM_BRAKE") (class "Default")
      (node (ref "JP8") (pin "1") (pinfunction "1_1") (pintype "passive"))
    )
    (net (code "19") (name "/HEPH_PWM_S") (class "Default")
      (node (ref "SV9") (pin "8") (pinfunction "8_8") (pintype "passive"))
    )
    (net (code "20") (name "/HEPH_STR_DIR2") (class "Default")
      (node (ref "JP41") (pin "2") (pinfunction "2_2") (pintype "passive"))
    )
    (net (code "21") (name "/HERA_HALL1") (class "Default")
      (node (ref "JP25") (pin "1") (pinfunction "1_1") (pintype "passive"))
      (node (ref "SV12") (pin "3") (pinfunction "3_3") (pintype "passive"))
    )
    (net (code "22") (name "/HERA_HALL2") (class "Default")
      (node (ref "JP42") (pin "2") (pinfunction "2_2") (pintype "passive"))
      (node (ref "SV12") (pin "4") (pinfunction "4_4") (pintype "passive"))
    )
    (net (code "23") (name "/HERA_SONAR1") (class "Default")
      (node (ref "JP9") (pin "1") (pinfunction "1_1") (pintype "passive"))
      (node (ref "SV11") (pin "7") (pinfunction "7_7") (pintype "passive"))
    )
    (net (code "24") (name "/HERA_SONAR2") (class "Default")
      (node (ref "JP3") (pin "1") (pinfunction "1_1") (pintype "passive"))
      (node (ref "SV11") (pin "8") (pinfunction "8_8") (pintype "passive"))
    )
    (net (code "25") (name "/HERA_SONAR3") (class "Default")
      (node (ref "JP17") (pin "1") (pinfunction "1_1") (pintype "passive"))
      (node (ref "SV11") (pin "9") (pinfunction "9_9") (pintype "passive"))
    )
    (net (code "26") (name "/HERA_SONAR4") (class "Default")
      (node (ref "JP26") (pin "1") (pinfunction "1_1") (pintype "passive"))
      (node (ref "SV11") (pin "10") (pinfunction "10_10") (pintype "passive"))
    )
    (net (code "27") (name "/HERA_SONAR5") (class "Default")
      (node (ref "JP4") (pin "1") (pinfunction "1_1") (pintype "passive"))
      (node (ref "SV12") (pin "1") (pinfunction "1_1") (pintype "passive"))
    )
    (net (code "28") (name "/HERA_STEER") (class "Default")
      (node (ref "JP33") (pin "2") (pinfunction "2_2") (pintype "passive"))
      (node (ref "SV12") (pin "5") (pinfunction "5_5") (pintype "passive"))
    )
    (net (code "29") (name "/HERA_TEMP1") (class "Default")
      (node (ref "JP34") (pin "2") (pinfunction "2_2") (pintype "passive"))
      (node (ref "SV12") (pin "6") (pinfunction "6_6") (pintype "passive"))
    )
    (net (code "30") (name "/HERA_TEMP2") (class "Default")
      (node (ref "JP35") (pin "2") (pinfunction "2_2") (pintype "passive"))
      (node (ref "SV12") (pin "7") (pinfunction "7_7") (pintype "passive"))
    )
    (net (code "31") (name "/HERA_TEMP3") (class "Default")
      (node (ref "JP36") (pin "2") (pinfunction "2_2") (pintype "passive"))
      (node (ref "SV12") (pin "8") (pinfunction "8_8") (pintype "passive"))
    )
    (net (code "32") (name "/HERA_TEMP4") (class "Default")
      (node (ref "JP1") (pin "1") (pinfunction "1_1") (pintype "passive"))
      (node (ref "SV12") (pin "9") (pinfunction "9_9") (pintype "passive"))
    )
    (net (code "33") (name "/HERA_TEMP5") (class "Default")
      (node (ref "JP2") (pin "1") (pinfunction "1_1") (pintype "passive"))
      (node (ref "SV12") (pin "10") (pinfunction "10_10") (pintype "passive"))
    )
    (net (code "34") (name "/HERMES_AUTOMAN") (class "Default")
      (node (ref "JP29") (pin "1") (pinfunction "1_1") (pintype "passive"))
    )
    (net (code "35") (name "/HERMES_PED_DET") (class "Default")
      (node (ref "JP5") (pin "1") (pinfunction "1_1") (pintype "passive"))
      (node (ref "SV7") (pin "8") (pinfunction "8_8") (pintype "passive"))
    )
    (net (code "36") (name "/I2C_SCL") (class "Default")
      (node (ref "JP27") (pin "1") (pinfunction "1_1") (pintype "passive"))
      (node (ref "JP53") (pin "1") (pinfunction "1_1") (pintype "passive"))
      (node (ref "R1") (pin "1") (pinfunction "1_1") (pintype "passive"))
      (node (ref "SV1") (pin "6") (pinfunction "6_6") (pintype "passive"))
      (node (ref "SV11") (pin "6") (pinfunction "6_6") (pintype "passive"))
      (node (ref "SV13") (pin "6") (pinfunction "6_6") (pintype "passive"))
      (node (ref "SV15") (pin "6") (pinfunction "6_6") (pintype "passive"))
      (node (ref "SV3") (pin "6") (pinfunction "6_6") (pintype "passive"))
      (node (ref "SV5") (pin "6") (pinfunction "6_6") (pintype "passive"))
      (node (ref "SV7") (pin "6") (pinfunction "6_6") (pintype "passive"))
      (node (ref "SV9") (pin "6") (pinfunction "6_6") (pintype "passive"))
    )
    (net (code "37") (name "/I2C_SDA") (class "Default")
      (node (ref "JP28") (pin "1") (pinfunction "1_1") (pintype "passive"))
      (node (ref "JP54") (pin "1") (pinfunction "1_1") (pintype "passive"))
      (node (ref "R2") (pin "1") (pinfunction "1_1") (pintype "passive"))
      (node (ref "SV1") (pin "5") (pinfunction "5_5") (pintype "passive"))
      (node (ref "SV11") (pin "5") (pinfunction "5_5") (pintype "passive"))
      (node (ref "SV13") (pin "5") (pinfunction "5_5") (pintype "passive"))
      (node (ref "SV15") (pin "5") (pinfunction "5_5") (pintype "passive"))
      (node (ref "SV3") (pin "5") (pinfunction "5_5") (pintype "passive"))
      (node (ref "SV5") (pin "5") (pinfunction "5_5") (pintype "passive"))
      (node (ref "SV7") (pin "5") (pinfunction "5_5") (pintype "passive"))
      (node (ref "SV9") (pin "5") (pinfunction "5_5") (pintype "passive"))
    )
    (net (code "38") (name "/IRIS_CLOCK") (class "Default")
      (node (ref "JP6") (pin "1") (pinfunction "1_1") (pintype "passive"))
      (node (ref "SV3") (pin "10") (pinfunction "10_10") (pintype "passive"))
    )
    (net (code "39") (name "/IRIS_DATA") (class "Default")
      (node (ref "JP22") (pin "1") (pinfunction "1_1") (pintype "passive"))
      (node (ref "SV3") (pin "9") (pinfunction "9_9") (pintype "passive"))
    )
    (net (code "40") (name "/IRIS_UART_RX") (class "Default")
      (node (ref "JP24") (pin "1") (pinfunction "1_1") (pintype "passive"))
      (node (ref "SV3") (pin "7") (pinfunction "7_7") (pintype "passive"))
    )
    (net (code "41") (name "/IRIS_UART_TX") (class "Default")
      (node (ref "JP23") (pin "1") (pinfunction "1_1") (pintype "passive"))
      (node (ref "SV3") (pin "8") (pinfunction "8_8") (pintype "passive"))
    )
    (net (code "42") (name "/JANUS_AUTOMAN") (class "Default")
      (node (ref "JP48") (pin "2") (pinfunction "2_2") (pintype "passive"))
      (node (ref "SV5") (pin "9") (pinfunction "9_9") (pintype "passive"))
    )
    (net (code "43") (name "/JANUS_F") (class "Default")
      (node (ref "JP47") (pin "2") (pinfunction "2_2") (pintype "passive"))
      (node (ref "SV5") (pin "7") (pinfunction "7_7") (pintype "passive"))
    )
    (net (code "44") (name "/JANUS_R") (class "Default")
      (node (ref "JP46") (pin "2") (pinfunction "2_2") (pintype "passive"))
      (node (ref "SV5") (pin "8") (pinfunction "8_8") (pintype "passive"))
    )
    (net (code "45") (name "/JTAG_NRST") (class "Default")
      (node (ref "J1") (pin "10") (pinfunction "10_10") (pintype "bidirectional"))
      (node (ref "JP69") (pin "1") (pinfunction "1_1") (pintype "passive"))
    )
    (net (code "46") (name "/JTAG_SWO") (class "Default")
      (node (ref "J1") (pin "6") (pinfunction "6_6") (pintype "bidirectional"))
      (node (ref "JP67") (pin "1") (pinfunction "1_1") (pintype "passive"))
    )
    (net (code "47") (name "/JTAG_TDI") (class "Default")
      (node (ref "J1") (pin "8") (pinfunction "8_8") (pintype "bidirectional"))
      (node (ref "JP68") (pin "1") (pinfunction "1_1") (pintype "passive"))
    )
    (net (code "48") (name "/JTAG_VREF") (class "Default")
      (node (ref "J1") (pin "1") (pinfunction "1_1") (pintype "bidirectional"))
      (node (ref "JP66") (pin "2") (pinfunction "2_2") (pintype "passive"))
    )
    (net (code "49") (name "/LED1_A") (class "Default")
      (node (ref "LED1") (pin "A") (pinfunction "A_A") (pintype "passive"))
      (node (ref "R3") (pin "1") (pinfunction "1_1") (pintype "passive"))
    )
    (net (code "50") (name "/LED1_C") (class "Default")
      (node (ref "LED1") (pin "C") (pinfunction "C_C") (pintype "passive"))
      (node (ref "Q1") (pin "3") (pinfunction "D_3") (pintype "passive"))
    )
    (net (code "51") (name "/LED1_G") (class "Default")
      (node (ref "JP55") (pin "1") (pinfunction "1_1") (pintype "passive"))
      (node (ref "Q1") (pin "1") (pinfunction "G_1") (pintype "passive"))
      (node (ref "R24") (pin "1") (pinfunction "1_1") (pintype "passive"))
    )
    (net (code "52") (name "/LED2_A") (class "Default")
      (node (ref "LED2") (pin "A") (pinfunction "A_A") (pintype "passive"))
      (node (ref "R4") (pin "1") (pinfunction "1_1") (pintype "passive"))
    )
    (net (code "53") (name "/LED2_C") (class "Default")
      (node (ref "LED2") (pin "C") (pinfunction "C_C") (pintype "passive"))
      (node (ref "Q2") (pin "3") (pinfunction "D_3") (pintype "passive"))
    )
    (net (code "54") (name "/LED2_G") (class "Default")
      (node (ref "JP56") (pin "1") (pinfunction "1_1") (pintype "passive"))
      (node (ref "Q2") (pin "1") (pinfunction "G_1") (pintype "passive"))
      (node (ref "R25") (pin "1") (pinfunction "1_1") (pintype "passive"))
    )
    (net (code "55") (name "/LED3_A") (class "Default")
      (node (ref "LED3") (pin "A") (pinfunction "A_A") (pintype "passive"))
      (node (ref "R5") (pin "1") (pinfunction "1_1") (pintype "passive"))
    )
    (net (code "56") (name "/LED3_C") (class "Default")
      (node (ref "LED3") (pin "C") (pinfunction "C_C") (pintype "passive"))
      (node (ref "Q3") (pin "3") (pinfunction "D_3") (pintype "passive"))
    )
    (net (code "57") (name "/LED3_G") (class "Default")
      (node (ref "JP57") (pin "1") (pinfunction "1_1") (pintype "passive"))
      (node (ref "Q3") (pin "1") (pinfunction "G_1") (pintype "passive"))
      (node (ref "R26") (pin "1") (pinfunction "1_1") (pintype "passive"))
    )
    (net (code "58") (name "/LED4_A") (class "Default")
      (node (ref "LED4") (pin "A") (pinfunction "A_A") (pintype "passive"))
      (node (ref "R6") (pin "1") (pinfunction "1_1") (pintype "passive"))
    )
    (net (code "59") (name "/LED4_C") (class "Default")
      (node (ref "LED4") (pin "C") (pinfunction "C_C") (pintype "passive"))
      (node (ref "Q4") (pin "3") (pinfunction "D_3") (pintype "passive"))
    )
    (net (code "60") (name "/LED4_G") (class "Default")
      (node (ref "JP58") (pin "1") (pinfunction "1_1") (pintype "passive"))
      (node (ref "Q4") (pin "1") (pinfunction "G_1") (pintype "passive"))
      (node (ref "R27") (pin "1") (pinfunction "1_1") (pintype "passive"))
    )
    (net (code "61") (name "/LED5_A") (class "Default")
      (node (ref "LED5") (pin "A") (pinfunction "A_A") (pintype "passive"))
      (node (ref "R7") (pin "1") (pinfunction "1_1") (pintype "passive"))
    )
    (net (code "62") (name "/LED5_C") (class "Default")
      (node (ref "LED5") (pin "C") (pinfunction "C_C") (pintype "passive"))
      (node (ref "Q5") (pin "3") (pinfunction "D_3") (pintype "passive"))
    )
    (net (code "63") (name "/LED5_G") (class "Default")
      (node (ref "JP59") (pin "1") (pinfunction "1_1") (pintype "passive"))
      (node (ref "Q5") (pin "1") (pinfunction "G_1") (pintype "passive"))
      (node (ref "R32") (pin "1") (pinfunction "1_1") (pintype "passive"))
    )
    (net (code "64") (name "/LED6_A") (class "Default")
      (node (ref "LED6") (pin "A") (pinfunction "A_A") (pintype "passive"))
      (node (ref "R8") (pin "1") (pinfunction "1_1") (pintype "passive"))
    )
    (net (code "65") (name "/LED6_C") (class "Default")
      (node (ref "LED6") (pin "C") (pinfunction "C_C") (pintype "passive"))
      (node (ref "Q6") (pin "3") (pinfunction "D_3") (pintype "passive"))
    )
    (net (code "66") (name "/LED6_G") (class "Default")
      (node (ref "JP60") (pin "1") (pinfunction "1_1") (pintype "passive"))
      (node (ref "Q6") (pin "1") (pinfunction "G_1") (pintype "passive"))
      (node (ref "R33") (pin "1") (pinfunction "1_1") (pintype "passive"))
    )
    (net (code "67") (name "/LED13_R") (class "Default")
      (node (ref "LED13") (pin "A") (pinfunction "A_A") (pintype "passive"))
      (node (ref "R21") (pin "1") (pinfunction "1_1") (pintype "passive"))
    )
    (net (code "68") (name "/LED14_R") (class "Default")
      (node (ref "LED14") (pin "A") (pinfunction "A_A") (pintype "passive"))
      (node (ref "R22") (pin "1") (pinfunction "1_1") (pintype "passive"))
    )
    (net (code "69") (name "/LED15_R") (class "Default")
      (node (ref "LED15") (pin "A") (pinfunction "A_A") (pintype "passive"))
      (node (ref "R23") (pin "1") (pinfunction "1_1") (pintype "passive"))
    )
    (net (code "70") (name "/MCU_BOOT0") (class "Default")
      (node (ref "JP88") (pin "1") (pinfunction "1_1") (pintype "passive"))
      (node (ref "R15") (pin "1") (pinfunction "1_1") (pintype "passive"))
      (node (ref "R17") (pin "2") (pinfunction "2_2") (pintype "passive"))
      (node (ref "U1") (pin "60") (pinfunction "BOOT0_60") (pintype "bidirectional"))
    )
    (net (code "71") (name "/MCU_BOOT1") (class "Default")
      (node (ref "JP19") (pin "1") (pinfunction "1_1") (pintype "passive"))
      (node (ref "R16") (pin "1") (pinfunction "1_1") (pintype "passive"))
      (node (ref "R18") (pin "2") (pinfunction "2_2") (pintype "passive"))
    )
    (net (code "72") (name "/MCU_NRST") (class "Default")
      (node (ref "C8") (pin "1") (pinfunction "1_1") (pintype "passive"))
      (node (ref "JP69") (pin "2") (pinfunction "2_2") (pintype "passive"))
      (node (ref "R14") (pin "1") (pinfunction "1_1") (pintype "passive"))
      (node (ref "S1") (pin "1") (pinfunction "S_1") (pintype "passive"))
      (node (ref "S1") (pin "2") (pinfunction "S1_2") (pintype "passive"))
      (node (ref "U1") (pin "7") (pinfunction "NRST_7") (pintype "bidirectional"))
    )
    (net (code "73") (name "/MCU_PA0") (class "Default")
      (node (ref "JP1") (pin "2") (pinfunction "2_2") (pintype "passive"))
      (node (ref "U1") (pin "14") (pinfunction "PA0-WKUP_14") (pintype "bidirectional"))
    )
    (net (code "74") (name "/MCU_PA1") (class "Default")
      (node (ref "JP2") (pin "2") (pinfunction "2_2") (pintype "passive"))
      (node (ref "U1") (pin "15") (pinfunction "PA1_15") (pintype "bidirectional"))
    )
    (net (code "75") (name "/MCU_PA2") (class "Default")
      (node (ref "JP3") (pin "2") (pinfunction "2_2") (pintype "passive"))
      (node (ref "U1") (pin "16") (pinfunction "PA2_16") (pintype "bidirectional"))
    )
    (net (code "76") (name "/MCU_PA3") (class "Default")
      (node (ref "JP4") (pin "2") (pinfunction "2_2") (pintype "passive"))
      (node (ref "U1") (pin "17") (pinfunction "PA3_17") (pintype "bidirectional"))
    )
    (net (code "77") (name "/MCU_PA4") (class "Default")
      (node (ref "JP5") (pin "2") (pinfunction "2_2") (pintype "passive"))
      (node (ref "U1") (pin "20") (pinfunction "PA4_20") (pintype "bidirectional"))
    )
    (net (code "78") (name "/MCU_PA5") (class "Default")
      (node (ref "JP6") (pin "2") (pinfunction "2_2") (pintype "passive"))
      (node (ref "U1") (pin "21") (pinfunction "PA5_21") (pintype "bidirectional"))
    )
    (net (code "79") (name "/MCU_PA6") (class "Default")
      (node (ref "JP7") (pin "2") (pinfunction "2_2") (pintype "passive"))
      (node (ref "U1") (pin "22") (pinfunction "PA6_22") (pintype "bidirectional"))
    )
    (net (code "80") (name "/MCU_PA7") (class "Default")
      (node (ref "JP8") (pin "2") (pinfunction "2_2") (pintype "passive"))
      (node (ref "U1") (pin "23") (pinfunction "PA7_23") (pintype "bidirectional"))
    )
    (net (code "81") (name "/MCU_PA8") (class "Default")
      (node (ref "JP9") (pin "2") (pinfunction "2_2") (pintype "passive"))
      (node (ref "U1") (pin "41") (pinfunction "PA8_41") (pintype "bidirectional"))
    )
    (net (code "82") (name "/MCU_PA9") (class "Default")
      (node (ref "JP10") (pin "2") (pinfunction "2_2") (pintype "passive"))
      (node (ref "U1") (pin "42") (pinfunction "PA9_42") (pintype "bidirectional"))
    )
    (net (code "83") (name "/MCU_PA10") (class "Default")
      (node (ref "JP11") (pin "2") (pinfunction "2_2") (pintype "passive"))
      (node (ref "U1") (pin "43") (pinfunction "PA10_43") (pintype "bidirectional"))
    )
    (net (code "84") (name "/MCU_PA11") (class "Default")
      (node (ref "JP12") (pin "2") (pinfunction "2_2") (pintype "passive"))
      (node (ref "U1") (pin "44") (pinfunction "PA11_44") (pintype "bidirectional"))
    )
    (net (code "85") (name "/MCU_PA12") (class "Default")
      (node (ref "JP13") (pin "2") (pinfunction "2_2") (pintype "passive"))
      (node (ref "U1") (pin "45") (pinfunction "PA12_45") (pintype "bidirectional"))
    )
    (net (code "86") (name "/MCU_PA13") (class "Default")
      (node (ref "JP14") (pin "2") (pinfunction "2_2") (pintype "passive"))
      (node (ref "U1") (pin "46") (pinfunction "PA13_46") (pintype "bidirectional"))
    )
    (net (code "87") (name "/MCU_PA14") (class "Default")
      (node (ref "JP15") (pin "2") (pinfunction "2_2") (pintype "passive"))
      (node (ref "U1") (pin "49") (pinfunction "PA14_49") (pintype "bidirectional"))
    )
    (net (code "88") (name "/MCU_PA15") (class "Default")
      (node (ref "JP16") (pin "2") (pinfunction "2_2") (pintype "passive"))
      (node (ref "U1") (pin "50") (pinfunction "PA15_50") (pintype "bidirectional"))
    )
    (net (code "89") (name "/MCU_PB0") (class "Default")
      (node (ref "JP17") (pin "2") (pinfunction "2_2") (pintype "passive"))
      (node (ref "U1") (pin "26") (pinfunction "PB0_26") (pintype "bidirectional"))
    )
    (net (code "90") (name "/MCU_PB1") (class "Default")
      (node (ref "JP18") (pin "2") (pinfunction "2_2") (pintype "passive"))
      (node (ref "U1") (pin "27") (pinfunction "PB1_27") (pintype "bidirectional"))
    )
    (net (code "91") (name "/MCU_PB2") (class "Default")
      (node (ref "JP19") (pin "2") (pinfunction "2_2") (pintype "passive"))
      (node (ref "U1") (pin "28") (pinfunction "PB2_28") (pintype "bidirectional"))
    )
    (net (code "92") (name "/MCU_PB3") (class "Default")
      (node (ref "JP20") (pin "2") (pinfunction "2_2") (pintype "passive"))
      (node (ref "U1") (pin "55") (pinfunction "PB3_55") (pintype "bidirectional"))
    )
    (net (code "93") (name "/MCU_PB4") (class "Default")
      (node (ref "JP21") (pin "2") (pinfunction "2_2") (pintype "passive"))
      (node (ref "U1") (pin "56") (pinfunction "PB4_56") (pintype "bidirectional"))
    )
    (net (code "94") (name "/MCU_PB5") (class "Default")
      (node (ref "JP22") (pin "2") (pinfunction "2_2") (pintype "passive"))
      (node (ref "U1") (pin "57") (pinfunction "PB5_57") (pintype "bidirectional"))
    )
    (net (code "95") (name "/MCU_PB6") (class "Default")
      (node (ref "JP23") (pin "2") (pinfunction "2_2") (pintype "passive"))
      (node (ref "U1") (pin "58") (pinfunction "PB6_58") (pintype "bidirectional"))
    )
    (net (code "96") (name "/MCU_PB7") (class "Default")
      (node (ref "JP24") (pin "2") (pinfunction "2_2") (pintype "passive"))
      (node (ref "U1") (pin "59") (pinfunction "PB7_59") (pintype "bidirectional"))
    )
    (net (code "97") (name "/MCU_PB8") (class "Default")
      (node (ref "JP25") (pin "2") (pinfunction "2_2") (pintype "passive"))
      (node (ref "U1") (pin "61") (pinfunction "PB8_61") (pintype "bidirectional"))
    )
    (net (code "98") (name "/MCU_PB9") (class "Default")
      (node (ref "JP26") (pin "2") (pinfunction "2_2") (pintype "passive"))
      (node (ref "U1") (pin "62") (pinfunction "PB9_62") (pintype "bidirectional"))
    )
    (net (code "99") (name "/MCU_PB10") (class "Default")
      (node (ref "JP27") (pin "2") (pinfunction "2_2") (pintype "passive"))
      (node (ref "U1") (pin "29") (pinfunction "PB10_29") (pintype "bidirectional"))
    )
    (net (code "100") (name "/MCU_PB11") (class "Default")
      (node (ref "JP28") (pin "2") (pinfunction "2_2") (pintype "passive"))
      (node (ref "U1") (pin "30") (pinfunction "PB11_30") (pintype "bidirectional"))
    )
    (net (code "101") (name "/MCU_PB12") (class "Default")
      (node (ref "JP29") (pin "2") (pinfunction "2_2") (pintype "passive"))
      (node (ref "U1") (pin "33") (pinfunction "PB12_33") (pintype "bidirectional"))
    )
    (net (code "102") (name "/MCU_PB13") (class "Default")
      (node (ref "JP30") (pin "2") (pinfunction "2_2") (pintype "passive"))
      (node (ref "U1") (pin "34") (pinfunction "PB13_34") (pintype "bidirectional"))
    )
    (net (code "103") (name "/MCU_PB14") (class "Default")
      (node (ref "JP31") (pin "2") (pinfunction "2_2") (pintype "passive"))
      (node (ref "U1") (pin "35") (pinfunction "PB14_35") (pintype "bidirectional"))
    )
    (net (code "104") (name "/MCU_PB15") (class "Default")
      (node (ref "JP32") (pin "2") (pinfunction "2_2") (pintype "passive"))
      (node (ref "U1") (pin "36") (pinfunction "PB15_36") (pintype "bidirectional"))
    )
    (net (code "105") (name "/MCU_PC0") (class "Default")
      (node (ref "JP33") (pin "1") (pinfunction "1_1") (pintype "passive"))
      (node (ref "U1") (pin "8") (pinfunction "PC0_8") (pintype "bidirectional"))
    )
    (net (code "106") (name "/MCU_PC1") (class "Default")
      (node (ref "JP34") (pin "1") (pinfunction "1_1") (pintype "passive"))
      (node (ref "U1") (pin "9") (pinfunction "PC1_9") (pintype "bidirectional"))
    )
    (net (code "107") (name "/MCU_PC2") (class "Default")
      (node (ref "JP35") (pin "1") (pinfunction "1_1") (pintype "passive"))
      (node (ref "U1") (pin "10") (pinfunction "PC2_10") (pintype "bidirectional"))
    )
    (net (code "108") (name "/MCU_PC3") (class "Default")
      (node (ref "JP36") (pin "1") (pinfunction "1_1") (pintype "passive"))
      (node (ref "U1") (pin "11") (pinfunction "PC3_11") (pintype "bidirectional"))
    )
    (net (code "109") (name "/MCU_PC4") (class "Default")
      (node (ref "JP37") (pin "1") (pinfunction "1_1") (pintype "passive"))
      (node (ref "U1") (pin "24") (pinfunction "PC4_24") (pintype "bidirectional"))
    )
    (net (code "110") (name "/MCU_PC5") (class "Default")
      (node (ref "JP38") (pin "1") (pinfunction "1_1") (pintype "passive"))
      (node (ref "U1") (pin "25") (pinfunction "PC5_25") (pintype "bidirectional"))
    )
    (net (code "111") (name "/MCU_PC6") (class "Default")
      (node (ref "JP39") (pin "1") (pinfunction "1_1") (pintype "passive"))
      (node (ref "U1") (pin "37") (pinfunction "PC6_37") (pintype "bidirectional"))
    )
    (net (code "112") (name "/MCU_PC7") (class "Default")
      (node (ref "JP40") (pin "1") (pinfunction "1_1") (pintype "passive"))
      (node (ref "U1") (pin "38") (pinfunction "PC7_38") (pintype "bidirectional"))
    )
    (net (code "113") (name "/MCU_PC8") (class "Default")
      (node (ref "JP41") (pin "1") (pinfunction "1_1") (pintype "passive"))
      (node (ref "U1") (pin "39") (pinfunction "PC8_39") (pintype "bidirectional"))
    )
    (net (code "114") (name "/MCU_PC9") (class "Default")
      (node (ref "JP42") (pin "1") (pinfunction "1_1") (pintype "passive"))
      (node (ref "U1") (pin "40") (pinfunction "PC9_40") (pintype "bidirectional"))
    )
    (net (code "115") (name "/MCU_PC10") (class "Default")
      (node (ref "JP43") (pin "1") (pinfunction "1_1") (pintype "passive"))
      (node (ref "U1") (pin "51") (pinfunction "PC10_51") (pintype "bidirectional"))
    )
    (net (code "116") (name "/MCU_PC11") (class "Default")
      (node (ref "JP44") (pin "1") (pinfunction "1_1") (pintype "passive"))
      (node (ref "U1") (pin "52") (pinfunction "PC11_52") (pintype "bidirectional"))
    )
    (net (code "117") (name "/MCU_PC12") (class "Default")
      (node (ref "JP45") (pin "1") (pinfunction "1_1") (pintype "passive"))
      (node (ref "U1") (pin "53") (pinfunction "PC12_53") (pintype "bidirectional"))
    )
    (net (code "118") (name "/MCU_PC13") (class "Default")
      (node (ref "JP46") (pin "1") (pinfunction "1_1") (pintype "passive"))
      (node (ref "U1") (pin "2") (pinfunction "PC13-RTC_AF1_2") (pintype "bidirectional"))
    )
    (net (code "119") (name "/MCU_PC14") (class "Default")
      (node (ref "JP47") (pin "1") (pinfunction "1_1") (pintype "passive"))
      (node (ref "U1") (pin "3") (pinfunction "PC14-OSC32_IN_3") (pintype "bidirectional"))
    )
    (net (code "120") (name "/MCU_PC15") (class "Default")
      (node (ref "JP48") (pin "1") (pinfunction "1_1") (pintype "passive"))
      (node (ref "U1") (pin "4") (pinfunction "PC15-OSC32_OUT_4") (pintype "bidirectional"))
    )
    (net (code "121") (name "/MCU_PD2") (class "Default")
      (node (ref "JP49") (pin "1") (pinfunction "1_1") (pintype "passive"))
      (node (ref "U1") (pin "54") (pinfunction "PD2_54") (pintype "bidirectional"))
    )
    (net (code "122") (name "/MCU_PH0") (class "Default")
      (node (ref "QG1") (pin "3") (pinfunction "OUT_3") (pintype "output"))
      (node (ref "U1") (pin "5") (pinfunction "PH0-OSC_IN_5") (pintype "bidirectional"))
    )
    (net (code "123") (name "/MCU_PH1") (class "Default")
      (node (ref "JP70") (pin "1") (pinfunction "1_1") (pintype "passive"))
      (node (ref "U1") (pin "6") (pinfunction "PH1-OSC_OUT_6") (pintype "bidirectional"))
    )
    (net (code "124") (name "/MCU_VCAP_1") (class "Default")
      (node (ref "C21") (pin "1") (pinfunction "1_1") (pintype "passive"))
      (node (ref "U1") (pin "31") (pinfunction "VCAP_1_31") (pintype "bidirectional"))
    )
    (net (code "125") (name "/MCU_VCAP_2") (class "Default")
      (node (ref "C20") (pin "1") (pinfunction "1_1") (pintype "passive"))
      (node (ref "U1") (pin "47") (pinfunction "VCAP_2_47") (pintype "bidirectional"))
    )
    (net (code "126") (name "/OLYMPUS_GPIO1") (class "Default")
      (node (ref "JP11") (pin "1") (pinfunction "1_1") (pintype "passive"))
      (node (ref "JP55") (pin "2") (pinfunction "2_2") (pintype "passive"))
    )
    (net (code "127") (name "/OLYMPUS_GPIO2") (class "Default")
      (node (ref "JP12") (pin "1") (pinfunction "1_1") (pintype "passive"))
      (node (ref "JP56") (pin "2") (pinfunction "2_2") (pintype "passive"))
    )
    (net (code "128") (name "/OLYMPUS_GPIO3") (class "Default")
      (node (ref "JP13") (pin "1") (pinfunction "1_1") (pintype "passive"))
      (node (ref "JP57") (pin "2") (pinfunction "2_2") (pintype "passive"))
    )
    (net (code "129") (name "/OLYMPUS_GPIO4") (class "Default")
      (node (ref "JP18") (pin "1") (pinfunction "1_1") (pintype "passive"))
      (node (ref "JP58") (pin "2") (pinfunction "2_2") (pintype "passive"))
      (node (ref "JP67") (pin "2") (pinfunction "2_2") (pintype "passive"))
    )
    (net (code "130") (name "/OLYMPUS_GPIO5") (class "Default")
      (node (ref "JP49") (pin "2") (pinfunction "2_2") (pintype "passive"))
      (node (ref "JP59") (pin "2") (pinfunction "2_2") (pintype "passive"))
    )
    (net (code "131") (name "/OLYMPUS_GPIO6") (class "Default")
      (node (ref "JP60") (pin "2") (pinfunction "2_2") (pintype "passive"))
      (node (ref "JP70") (pin "2") (pinfunction "2_2") (pintype "passive"))
    )
    (net (code "132") (name "/OLYMPUS_SWDCLK") (class "Default")
      (node (ref "J1") (pin "4") (pinfunction "4_4") (pintype "bidirectional"))
      (node (ref "JP15") (pin "1") (pinfunction "1_1") (pintype "passive"))
    )
    (net (code "133") (name "/OLYMPUS_SWDIO") (class "Default")
      (node (ref "J1") (pin "2") (pinfunction "2_2") (pintype "bidirectional"))
      (node (ref "JP14") (pin "1") (pinfunction "1_1") (pintype "passive"))
    )
    (net (code "134") (name "/OLYMPUS_USBDM") (class "Default")
      (node (ref "JP31") (pin "1") (pinfunction "1_1") (pintype "passive"))
    )
    (net (code "135") (name "/OLYMPUS_USBDN") (class "Default")
      (node (ref "X1") (pin "2") (pinfunction "2_2") (pintype "input"))
    )
    (net (code "136") (name "/OLYMPUS_USBDP") (class "Default")
      (node (ref "JP32") (pin "1") (pinfunction "1_1") (pintype "passive"))
      (node (ref "X1") (pin "3") (pinfunction "3_3") (pintype "input"))
    )
    (net (code "137") (name "/OLYMPUS_USBID") (class "Default")
      (node (ref "X1") (pin "4") (pinfunction "4_4") (pintype "input"))
    )
    (net (code "138") (name "/OLYMP_JTAG_SWO") (class "Default")
      (node (ref "JP20") (pin "1") (pinfunction "1_1") (pintype "passive"))
    )
    (net (code "139") (name "/OSC_EN") (class "Default")
      (node (ref "QG1") (pin "1") (pinfunction "E/D_1") (pintype "input"))
      (node (ref "R19") (pin "1") (pinfunction "1_1") (pintype "passive"))
    )
    (net (code "140") (name "/PP3V3") (class "Default")
      (node (ref "C1") (pin "1") (pinfunction "1_1") (pintype "passive"))
      (node (ref "C2") (pin "1") (pinfunction "1_1") (pintype "passive"))
      (node (ref "C3") (pin "1") (pinfunction "1_1") (pintype "passive"))
      (node (ref "C4") (pin "1") (pinfunction "1_1") (pintype "passive"))
      (node (ref "C5") (pin "1") (pinfunction "1_1") (pintype "passive"))
      (node (ref "C9") (pin "1") (pinfunction "1_1") (pintype "passive"))
      (node (ref "JP52") (pin "1") (pinfunction "1_1") (pintype "passive"))
      (node (ref "JP66") (pin "1") (pinfunction "1_1") (pintype "passive"))
      (node (ref "L1") (pin "2") (pinfunction "2_2") (pintype "passive"))
      (node (ref "QG1") (pin "4") (pinfunction "VCC_4") (pintype "power_in"))
      (node (ref "R1") (pin "2") (pinfunction "2_2") (pintype "passive"))
      (node (ref "R14") (pin "2") (pinfunction "2_2") (pintype "passive"))
      (node (ref "R15") (pin "2") (pinfunction "2_2") (pintype "passive"))
      (node (ref "R16") (pin "2") (pinfunction "2_2") (pintype "passive"))
      (node (ref "R19") (pin "2") (pinfunction "2_2") (pintype "passive"))
      (node (ref "R2") (pin "2") (pinfunction "2_2") (pintype "passive"))
      (node (ref "R21") (pin "2") (pinfunction "2_2") (pintype "passive"))
      (node (ref "SV1") (pin "3") (pinfunction "3_3") (pintype "passive"))
      (node (ref "SV11") (pin "3") (pinfunction "3_3") (pintype "passive"))
      (node (ref "SV13") (pin "3") (pinfunction "3_3") (pintype "passive"))
      (node (ref "SV15") (pin "3") (pinfunction "3_3") (pintype "passive"))
      (node (ref "SV3") (pin "3") (pinfunction "3_3") (pintype "passive"))
      (node (ref "SV5") (pin "3") (pinfunction "3_3") (pintype "passive"))
      (node (ref "SV7") (pin "3") (pinfunction "3_3") (pintype "passive"))
      (node (ref "SV9") (pin "3") (pinfunction "3_3") (pintype "passive"))
      (node (ref "U1") (pin "19") (pinfunction "VDD_19") (pintype "bidirectional"))
      (node (ref "U1") (pin "32") (pinfunction "VDD_32") (pintype "bidirectional"))
      (node (ref "U1") (pin "48") (pinfunction "VDD_48") (pintype "bidirectional"))
      (node (ref "U1") (pin "64") (pinfunction "VDD_64") (pintype "bidirectional"))
    )
    (net (code "141") (name "/PP3V3A") (class "Default")
      (node (ref "C6") (pin "1") (pinfunction "1_1") (pintype "passive"))
      (node (ref "C7") (pin "1") (pinfunction "1_1") (pintype "passive"))
      (node (ref "L1") (pin "1") (pinfunction "1_1") (pintype "passive"))
      (node (ref "U1") (pin "13") (pinfunction "VDDA_13") (pintype "bidirectional"))
    )
    (net (code "142") (name "/PP5V") (class "Default")
      (node (ref "JP51") (pin "1") (pinfunction "1_1") (pintype "passive"))
      (node (ref "R22") (pin "2") (pinfunction "2_2") (pintype "passive"))
      (node (ref "R3") (pin "2") (pinfunction "2_2") (pintype "passive"))
      (node (ref "R4") (pin "2") (pinfunction "2_2") (pintype "passive"))
      (node (ref "R5") (pin "2") (pinfunction "2_2") (pintype "passive"))
      (node (ref "R6") (pin "2") (pinfunction "2_2") (pintype "passive"))
      (node (ref "R7") (pin "2") (pinfunction "2_2") (pintype "passive"))
      (node (ref "R8") (pin "2") (pinfunction "2_2") (pintype "passive"))
      (node (ref "SV1") (pin "2") (pinfunction "2_2") (pintype "passive"))
      (node (ref "SV11") (pin "2") (pinfunction "2_2") (pintype "passive"))
      (node (ref "SV13") (pin "2") (pinfunction "2_2") (pintype "passive"))
      (node (ref "SV15") (pin "2") (pinfunction "2_2") (pintype "passive"))
      (node (ref "SV3") (pin "2") (pinfunction "2_2") (pintype "passive"))
      (node (ref "SV5") (pin "2") (pinfunction "2_2") (pintype "passive"))
      (node (ref "SV7") (pin "2") (pinfunction "2_2") (pintype "passive"))
      (node (ref "SV9") (pin "2") (pinfunction "2_2") (pintype "passive"))
    )
    (net (code "143") (name "/PP12V") (class "Default")
      (node (ref "JP50") (pin "1") (pinfunction "1_1") (pintype "passive"))
      (node (ref "R23") (pin "2") (pinfunction "2_2") (pintype "passive"))
      (node (ref "SV1") (pin "1") (pinfunction "1_1") (pintype "passive"))
      (node (ref "SV11") (pin "1") (pinfunction "1_1") (pintype "passive"))
      (node (ref "SV13") (pin "1") (pinfunction "1_1") (pintype "passive"))
      (node (ref "SV15") (pin "1") (pinfunction "1_1") (pintype "passive"))
      (node (ref "SV3") (pin "1") (pinfunction "1_1") (pintype "passive"))
      (node (ref "SV5") (pin "1") (pinfunction "1_1") (pintype "passive"))
      (node (ref "SV7") (pin "1") (pinfunction "1_1") (pintype "passive"))
      (node (ref "SV9") (pin "1") (pinfunction "1_1") (pintype "passive"))
    )
    (net (code "144") (name "/ZEUS_GPIO") (class "Default")
      (node (ref "JP44") (pin "2") (pinfunction "2_2") (pintype "passive"))
      (node (ref "SV1") (pin "8") (pinfunction "8_8") (pintype "passive"))
    )
    (net (code "145") (name "/ZEUS_SHUTDOWN_N") (class "Default")
      (node (ref "JP10") (pin "1") (pinfunction "1_1") (pintype "passive"))
      (node (ref "SV1") (pin "7") (pinfunction "7_7") (pintype "passive"))
    )
    (net (code "146") (name "GND") (class "Default")
      (node (ref "C1") (pin "2") (pinfunction "2_2") (pintype "passive"))
      (node (ref "C2") (pin "2") (pinfunction "2_2") (pintype "passive"))
      (node (ref "C20") (pin "2") (pinfunction "2_2") (pintype "passive"))
      (node (ref "C21") (pin "2") (pinfunction "2_2") (pintype "passive"))
      (node (ref "C3") (pin "2") (pinfunction "2_2") (pintype "passive"))
      (node (ref "C4") (pin "2") (pinfunction "2_2") (pintype "passive"))
      (node (ref "C5") (pin "2") (pinfunction "2_2") (pintype "passive"))
      (node (ref "C6") (pin "2") (pinfunction "2_2") (pintype "passive"))
      (node (ref "C7") (pin "2") (pinfunction "2_2") (pintype "passive"))
      (node (ref "C8") (pin "2") (pinfunction "2_2") (pintype "passive"))
      (node (ref "C9") (pin "2") (pinfunction "2_2") (pintype "passive"))
      (node (ref "J1") (pin "3") (pinfunction "3_3") (pintype "bidirectional"))
      (node (ref "J1") (pin "5") (pinfunction "5_5") (pintype "bidirectional"))
      (node (ref "JP50") (pin "2") (pinfunction "2_2") (pintype "passive"))
      (node (ref "JP51") (pin "2") (pinfunction "2_2") (pintype "passive"))
      (node (ref "JP52") (pin "2") (pinfunction "2_2") (pintype "passive"))
      (node (ref "JP53") (pin "2") (pinfunction "2_2") (pintype "passive"))
      (node (ref "JP54") (pin "2") (pinfunction "2_2") (pintype "passive"))
      (node (ref "LED13") (pin "C") (pinfunction "C_C") (pintype "passive"))
      (node (ref "LED14") (pin "C") (pinfunction "C_C") (pintype "passive"))
      (node (ref "LED15") (pin "C") (pinfunction "C_C") (pintype "passive"))
      (node (ref "Q1") (pin "2") (pinfunction "S_2") (pintype "passive"))
      (node (ref "Q2") (pin "2") (pinfunction "S_2") (pintype "passive"))
      (node (ref "Q3") (pin "2") (pinfunction "S_2") (pintype "passive"))
      (node (ref "Q4") (pin "2") (pinfunction "S_2") (pintype "passive"))
      (node (ref "Q5") (pin "2") (pinfunction "S_2") (pintype "passive"))
      (node (ref "Q6") (pin "2") (pinfunction "S_2") (pintype "passive"))
      (node (ref "QG1") (pin "2") (pinfunction "GND_2") (pintype "power_in"))
      (node (ref "R17") (pin "1") (pinfunction "1_1") (pintype "passive"))
      (node (ref "R18") (pin "1") (pinfunction "1_1") (pintype "passive"))
      (node (ref "R24") (pin "2") (pinfunction "2_2") (pintype "passive"))
      (node (ref "R25") (pin "2") (pinfunction "2_2") (pintype "passive"))
      (node (ref "R26") (pin "2") (pinfunction "2_2") (pintype "passive"))
      (node (ref "R27") (pin "2") (pinfunction "2_2") (pintype "passive"))
      (node (ref "R32") (pin "2") (pinfunction "2_2") (pintype "passive"))
      (node (ref "R33") (pin "2") (pinfunction "2_2") (pintype "passive"))
      (node (ref "S1") (pin "3") (pinfunction "P_3") (pintype "passive"))
      (node (ref "S1") (pin "4") (pinfunction "P1_4") (pintype "passive"))
      (node (ref "SV1") (pin "4") (pinfunction "4_4") (pintype "passive"))
      (node (ref "SV11") (pin "4") (pinfunction "4_4") (pintype "passive"))
      (node (ref "SV13") (pin "4") (pinfunction "4_4") (pintype "passive"))
      (node (ref "SV15") (pin "4") (pinfunction "4_4") (pintype "passive"))
      (node (ref "SV3") (pin "4") (pinfunction "4_4") (pintype "passive"))
      (node (ref "SV5") (pin "4") (pinfunction "4_4") (pintype "passive"))
      (node (ref "SV7") (pin "4") (pinfunction "4_4") (pintype "passive"))
      (node (ref "SV9") (pin "4") (pinfunction "4_4") (pintype "passive"))
      (node (ref "U1") (pin "12") (pinfunction "VSSA_12") (pintype "bidirectional"))
      (node (ref "U1") (pin "18") (pinfunction "VSS_18") (pintype "bidirectional"))
      (node (ref "U1") (pin "63") (pinfunction "VSS_63") (pintype "bidirectional"))
      (node (ref "X1") (pin "5") (pinfunction "5_5") (pintype "input"))
    )
    (net (code "147") (name "unconnected-(J1-Pad7)") (class "Default")
      (node (ref "J1") (pin "7") (pinfunction "7_7") (pintype "bidirectional"))
    )
    (net (code "148") (name "unconnected-(J1-Pad9)") (class "Default")
      (node (ref "J1") (pin "9") (pinfunction "9_9") (pintype "bidirectional"))
    )
    (net (code "149") (name "unconnected-(JP72-Pad1)") (class "Default")
      (node (ref "JP72") (pin "1") (pinfunction "1_1") (pintype "passive"))
    )
    (net (code "150") (name "unconnected-(JP73-Pad1)") (class "Default")
      (node (ref "JP73") (pin "1") (pinfunction "1_1") (pintype "passive"))
    )
    (net (code "151") (name "unconnected-(JP74-Pad1)") (class "Default")
      (node (ref "JP74") (pin "1") (pinfunction "1_1") (pintype "passive"))
    )
    (net (code "152") (name "unconnected-(JP75-Pad1)") (class "Default")
      (node (ref "JP75") (pin "1") (pinfunction "1_1") (pintype "passive"))
    )
    (net (code "153") (name "unconnected-(JP76-Pad1)") (class "Default")
      (node (ref "JP76") (pin "1") (pinfunction "1_1") (pintype "passive"))
    )
    (net (code "154") (name "unconnected-(JP77-Pad1)") (class "Default")
      (node (ref "JP77") (pin "1") (pinfunction "1_1") (pintype "passive"))
    )
    (net (code "155") (name "unconnected-(JP78-Pad1)") (class "Default")
      (node (ref "JP78") (pin "1") (pinfunction "1_1") (pintype "passive"))
    )
    (net (code "156") (name "unconnected-(JP79-Pad1)") (class "Default")
      (node (ref "JP79") (pin "1") (pinfunction "1_1") (pintype "passive"))
    )
    (net (code "157") (name "unconnected-(JP80-Pad1)") (class "Default")
      (node (ref "JP80") (pin "1") (pinfunction "1_1") (pintype "passive"))
    )
    (net (code "158") (name "unconnected-(JP81-Pad1)") (class "Default")
      (node (ref "JP81") (pin "1") (pinfunction "1_1") (pintype "passive"))
    )
    (net (code "159") (name "unconnected-(JP82-Pad1)") (class "Default")
      (node (ref "JP82") (pin "1") (pinfunction "1_1") (pintype "passive"))
    )
    (net (code "160") (name "unconnected-(JP83-Pad1)") (class "Default")
      (node (ref "JP83") (pin "1") (pinfunction "1_1") (pintype "passive"))
    )
    (net (code "161") (name "unconnected-(JP84-Pad1)") (class "Default")
      (node (ref "JP84") (pin "1") (pinfunction "1_1") (pintype "passive"))
    )
    (net (code "162") (name "unconnected-(JP85-Pad1)") (class "Default")
      (node (ref "JP85") (pin "1") (pinfunction "1_1") (pintype "passive"))
    )
    (net (code "163") (name "unconnected-(JP86-Pad1)") (class "Default")
      (node (ref "JP86") (pin "1") (pinfunction "1_1") (pintype "passive"))
    )
    (net (code "164") (name "unconnected-(JP87-Pad1)") (class "Default")
      (node (ref "JP87") (pin "1") (pinfunction "1_1") (pintype "passive"))
    )
    (net (code "165") (name "unconnected-(JP88-Pad2)") (class "Default")
      (node (ref "JP88") (pin "2") (pinfunction "2_2") (pintype "passive"))
    )
    (net (code "166") (name "unconnected-(SV1-Pad9)") (class "Default")
      (node (ref "SV1") (pin "9") (pinfunction "9_9") (pintype "passive"))
    )
    (net (code "167") (name "unconnected-(SV1-Pad10)") (class "Default")
      (node (ref "SV1") (pin "10") (pinfunction "10_10") (pintype "passive"))
    )
    (net (code "168") (name "unconnected-(SV2-Pad1)") (class "Default")
      (node (ref "SV2") (pin "1") (pinfunction "1_1") (pintype "passive"))
    )
    (net (code "169") (name "unconnected-(SV2-Pad2)") (class "Default")
      (node (ref "SV2") (pin "2") (pinfunction "2_2") (pintype "passive"))
    )
    (net (code "170") (name "unconnected-(SV2-Pad3)") (class "Default")
      (node (ref "SV2") (pin "3") (pinfunction "3_3") (pintype "passive"))
    )
    (net (code "171") (name "unconnected-(SV2-Pad4)") (class "Default")
      (node (ref "SV2") (pin "4") (pinfunction "4_4") (pintype "passive"))
    )
    (net (code "172") (name "unconnected-(SV2-Pad5)") (class "Default")
      (node (ref "SV2") (pin "5") (pinfunction "5_5") (pintype "passive"))
    )
    (net (code "173") (name "unconnected-(SV2-Pad6)") (class "Default")
      (node (ref "SV2") (pin "6") (pinfunction "6_6") (pintype "passive"))
    )
    (net (code "174") (name "unconnected-(SV2-Pad7)") (class "Default")
      (node (ref "SV2") (pin "7") (pinfunction "7_7") (pintype "passive"))
    )
    (net (code "175") (name "unconnected-(SV2-Pad8)") (class "Default")
      (node (ref "SV2") (pin "8") (pinfunction "8_8") (pintype "passive"))
    )
    (net (code "176") (name "unconnected-(SV2-Pad9)") (class "Default")
      (node (ref "SV2") (pin "9") (pinfunction "9_9") (pintype "passive"))
    )
    (net (code "177") (name "unconnected-(SV2-Pad10)") (class "Default")
      (node (ref "SV2") (pin "10") (pinfunction "10_10") (pintype "passive"))
    )
    (net (code "178") (name "unconnected-(SV4-Pad1)") (class "Default")
      (node (ref "SV4") (pin "1") (pinfunction "1_1") (pintype "passive"))
    )
    (net (code "179") (name "unconnected-(SV4-Pad2)") (class "Default")
      (node (ref "SV4") (pin "2") (pinfunction "2_2") (pintype "passive"))
    )
    (net (code "180") (name "unconnected-(SV4-Pad3)") (class "Default")
      (node (ref "SV4") (pin "3") (pinfunction "3_3") (pintype "passive"))
    )
    (net (code "181") (name "unconnected-(SV4-Pad4)") (class "Default")
      (node (ref "SV4") (pin "4") (pinfunction "4_4") (pintype "passive"))
    )
    (net (code "182") (name "unconnected-(SV4-Pad5)") (class "Default")
      (node (ref "SV4") (pin "5") (pinfunction "5_5") (pintype "passive"))
    )
    (net (code "183") (name "unconnected-(SV4-Pad6)") (class "Default")
      (node (ref "SV4") (pin "6") (pinfunction "6_6") (pintype "passive"))
    )
    (net (code "184") (name "unconnected-(SV4-Pad7)") (class "Default")
      (node (ref "SV4") (pin "7") (pinfunction "7_7") (pintype "passive"))
    )
    (net (code "185") (name "unconnected-(SV4-Pad8)") (class "Default")
      (node (ref "SV4") (pin "8") (pinfunction "8_8") (pintype "passive"))
    )
    (net (code "186") (name "unconnected-(SV4-Pad9)") (class "Default")
      (node (ref "SV4") (pin "9") (pinfunction "9_9") (pintype "passive"))
    )
    (net (code "187") (name "unconnected-(SV4-Pad10)") (class "Default")
      (node (ref "SV4") (pin "10") (pinfunction "10_10") (pintype "passive"))
    )
    (net (code "188") (name "unconnected-(SV5-Pad10)") (class "Default")
      (node (ref "SV5") (pin "10") (pinfunction "10_10") (pintype "passive"))
    )
    (net (code "189") (name "unconnected-(SV6-Pad1)") (class "Default")
      (node (ref "SV6") (pin "1") (pinfunction "1_1") (pintype "passive"))
    )
    (net (code "190") (name "unconnected-(SV6-Pad2)") (class "Default")
      (node (ref "SV6") (pin "2") (pinfunction "2_2") (pintype "passive"))
    )
    (net (code "191") (name "unconnected-(SV6-Pad3)") (class "Default")
      (node (ref "SV6") (pin "3") (pinfunction "3_3") (pintype "passive"))
    )
    (net (code "192") (name "unconnected-(SV6-Pad4)") (class "Default")
      (node (ref "SV6") (pin "4") (pinfunction "4_4") (pintype "passive"))
    )
    (net (code "193") (name "unconnected-(SV6-Pad5)") (class "Default")
      (node (ref "SV6") (pin "5") (pinfunction "5_5") (pintype "passive"))
    )
    (net (code "194") (name "unconnected-(SV6-Pad6)") (class "Default")
      (node (ref "SV6") (pin "6") (pinfunction "6_6") (pintype "passive"))
    )
    (net (code "195") (name "unconnected-(SV6-Pad7)") (class "Default")
      (node (ref "SV6") (pin "7") (pinfunction "7_7") (pintype "passive"))
    )
    (net (code "196") (name "unconnected-(SV6-Pad8)") (class "Default")
      (node (ref "SV6") (pin "8") (pinfunction "8_8") (pintype "passive"))
    )
    (net (code "197") (name "unconnected-(SV6-Pad9)") (class "Default")
      (node (ref "SV6") (pin "9") (pinfunction "9_9") (pintype "passive"))
    )
    (net (code "198") (name "unconnected-(SV6-Pad10)") (class "Default")
      (node (ref "SV6") (pin "10") (pinfunction "10_10") (pintype "passive"))
    )
    (net (code "199") (name "unconnected-(SV7-Pad9)") (class "Default")
      (node (ref "SV7") (pin "9") (pinfunction "9_9") (pintype "passive"))
    )
    (net (code "200") (name "unconnected-(SV7-Pad10)") (class "Default")
      (node (ref "SV7") (pin "10") (pinfunction "10_10") (pintype "passive"))
    )
    (net (code "201") (name "unconnected-(SV8-Pad1)") (class "Default")
      (node (ref "SV8") (pin "1") (pinfunction "1_1") (pintype "passive"))
    )
    (net (code "202") (name "unconnected-(SV8-Pad2)") (class "Default")
      (node (ref "SV8") (pin "2") (pinfunction "2_2") (pintype "passive"))
    )
    (net (code "203") (name "unconnected-(SV8-Pad3)") (class "Default")
      (node (ref "SV8") (pin "3") (pinfunction "3_3") (pintype "passive"))
    )
    (net (code "204") (name "unconnected-(SV8-Pad4)") (class "Default")
      (node (ref "SV8") (pin "4") (pinfunction "4_4") (pintype "passive"))
    )
    (net (code "205") (name "unconnected-(SV8-Pad5)") (class "Default")
      (node (ref "SV8") (pin "5") (pinfunction "5_5") (pintype "passive"))
    )
    (net (code "206") (name "unconnected-(SV8-Pad6)") (class "Default")
      (node (ref "SV8") (pin "6") (pinfunction "6_6") (pintype "passive"))
    )
    (net (code "207") (name "unconnected-(SV8-Pad7)") (class "Default")
      (node (ref "SV8") (pin "7") (pinfunction "7_7") (pintype "passive"))
    )
    (net (code "208") (name "unconnected-(SV8-Pad8)") (class "Default")
      (node (ref "SV8") (pin "8") (pinfunction "8_8") (pintype "passive"))
    )
    (net (code "209") (name "unconnected-(SV8-Pad9)") (class "Default")
      (node (ref "SV8") (pin "9") (pinfunction "9_9") (pintype "passive"))
    )
    (net (code "210") (name "unconnected-(SV8-Pad10)") (class "Default")
      (node (ref "SV8") (pin "10") (pinfunction "10_10") (pintype "passive"))
    )
    (net (code "211") (name "unconnected-(SV10-Pad5)") (class "Default")
      (node (ref "SV10") (pin "5") (pinfunction "5_5") (pintype "passive"))
    )
    (net (code "212") (name "unconnected-(SV10-Pad6)") (class "Default")
      (node (ref "SV10") (pin "6") (pinfunction "6_6") (pintype "passive"))
    )
    (net (code "213") (name "unconnected-(SV10-Pad7)") (class "Default")
      (node (ref "SV10") (pin "7") (pinfunction "7_7") (pintype "passive"))
    )
    (net (code "214") (name "unconnected-(SV10-Pad8)") (class "Default")
      (node (ref "SV10") (pin "8") (pinfunction "8_8") (pintype "passive"))
    )
    (net (code "215") (name "unconnected-(SV10-Pad9)") (class "Default")
      (node (ref "SV10") (pin "9") (pinfunction "9_9") (pintype "passive"))
    )
    (net (code "216") (name "unconnected-(SV10-Pad10)") (class "Default")
      (node (ref "SV10") (pin "10") (pinfunction "10_10") (pintype "passive"))
    )
    (net (code "217") (name "unconnected-(SV12-Pad2)") (class "Default")
      (node (ref "SV12") (pin "2") (pinfunction "2_2") (pintype "passive"))
    )
    (net (code "218") (name "unconnected-(SV13-Pad10)") (class "Default")
      (node (ref "SV13") (pin "10") (pinfunction "10_10") (pintype "passive"))
    )
    (net (code "219") (name "unconnected-(SV14-Pad1)") (class "Default")
      (node (ref "SV14") (pin "1") (pinfunction "1_1") (pintype "passive"))
    )
    (net (code "220") (name "unconnected-(SV14-Pad2)") (class "Default")
      (node (ref "SV14") (pin "2") (pinfunction "2_2") (pintype "passive"))
    )
    (net (code "221") (name "unconnected-(SV14-Pad3)") (class "Default")
      (node (ref "SV14") (pin "3") (pinfunction "3_3") (pintype "passive"))
    )
    (net (code "222") (name "unconnected-(SV14-Pad4)") (class "Default")
      (node (ref "SV14") (pin "4") (pinfunction "4_4") (pintype "passive"))
    )
    (net (code "223") (name "unconnected-(SV14-Pad5)") (class "Default")
      (node (ref "SV14") (pin "5") (pinfunction "5_5") (pintype "passive"))
    )
    (net (code "224") (name "unconnected-(SV14-Pad6)") (class "Default")
      (node (ref "SV14") (pin "6") (pinfunction "6_6") (pintype "passive"))
    )
    (net (code "225") (name "unconnected-(SV14-Pad7)") (class "Default")
      (node (ref "SV14") (pin "7") (pinfunction "7_7") (pintype "passive"))
    )
    (net (code "226") (name "unconnected-(SV14-Pad8)") (class "Default")
      (node (ref "SV14") (pin "8") (pinfunction "8_8") (pintype "passive"))
    )
    (net (code "227") (name "unconnected-(SV14-Pad9)") (class "Default")
      (node (ref "SV14") (pin "9") (pinfunction "9_9") (pintype "passive"))
    )
    (net (code "228") (name "unconnected-(SV14-Pad10)") (class "Default")
      (node (ref "SV14") (pin "10") (pinfunction "10_10") (pintype "passive"))
    )
    (net (code "229") (name "unconnected-(SV15-Pad9)") (class "Default")
      (node (ref "SV15") (pin "9") (pinfunction "9_9") (pintype "passive"))
    )
    (net (code "230") (name "unconnected-(SV15-Pad10)") (class "Default")
      (node (ref "SV15") (pin "10") (pinfunction "10_10") (pintype "passive"))
    )
    (net (code "231") (name "unconnected-(SV16-Pad1)") (class "Default")
      (node (ref "SV16") (pin "1") (pinfunction "1_1") (pintype "passive"))
    )
    (net (code "232") (name "unconnected-(SV16-Pad2)") (class "Default")
      (node (ref "SV16") (pin "2") (pinfunction "2_2") (pintype "passive"))
    )
    (net (code "233") (name "unconnected-(SV16-Pad3)") (class "Default")
      (node (ref "SV16") (pin "3") (pinfunction "3_3") (pintype "passive"))
    )
    (net (code "234") (name "unconnected-(SV16-Pad4)") (class "Default")
      (node (ref "SV16") (pin "4") (pinfunction "4_4") (pintype "passive"))
    )
    (net (code "235") (name "unconnected-(SV16-Pad5)") (class "Default")
      (node (ref "SV16") (pin "5") (pinfunction "5_5") (pintype "passive"))
    )
    (net (code "236") (name "unconnected-(SV16-Pad6)") (class "Default")
      (node (ref "SV16") (pin "6") (pinfunction "6_6") (pintype "passive"))
    )
    (net (code "237") (name "unconnected-(SV16-Pad7)") (class "Default")
      (node (ref "SV16") (pin "7") (pinfunction "7_7") (pintype "passive"))
    )
    (net (code "238") (name "unconnected-(SV16-Pad8)") (class "Default")
      (node (ref "SV16") (pin "8") (pinfunction "8_8") (pintype "passive"))
    )
    (net (code "239") (name "unconnected-(SV16-Pad9)") (class "Default")
      (node (ref "SV16") (pin "9") (pinfunction "9_9") (pintype "passive"))
    )
    (net (code "240") (name "unconnected-(SV16-Pad10)") (class "Default")
      (node (ref "SV16") (pin "10") (pinfunction "10_10") (pintype "passive"))
    )
    (net (code "241") (name "unconnected-(U1-VBAT-Pad1)") (class "Default")
      (node (ref "U1") (pin "1") (pinfunction "VBAT_1") (pintype "bidirectional"))
    )
    (net (code "242") (name "unconnected-(X1-Pad1)") (class "Default")
      (node (ref "X1") (pin "1") (pinfunction "1_1") (pintype "input"))
    )
  )
)
